# axiom_beta_sensor_cmv12000_tht_v0_16_r1_.net
KiCad netlist of a schematic drawn in EAGLE
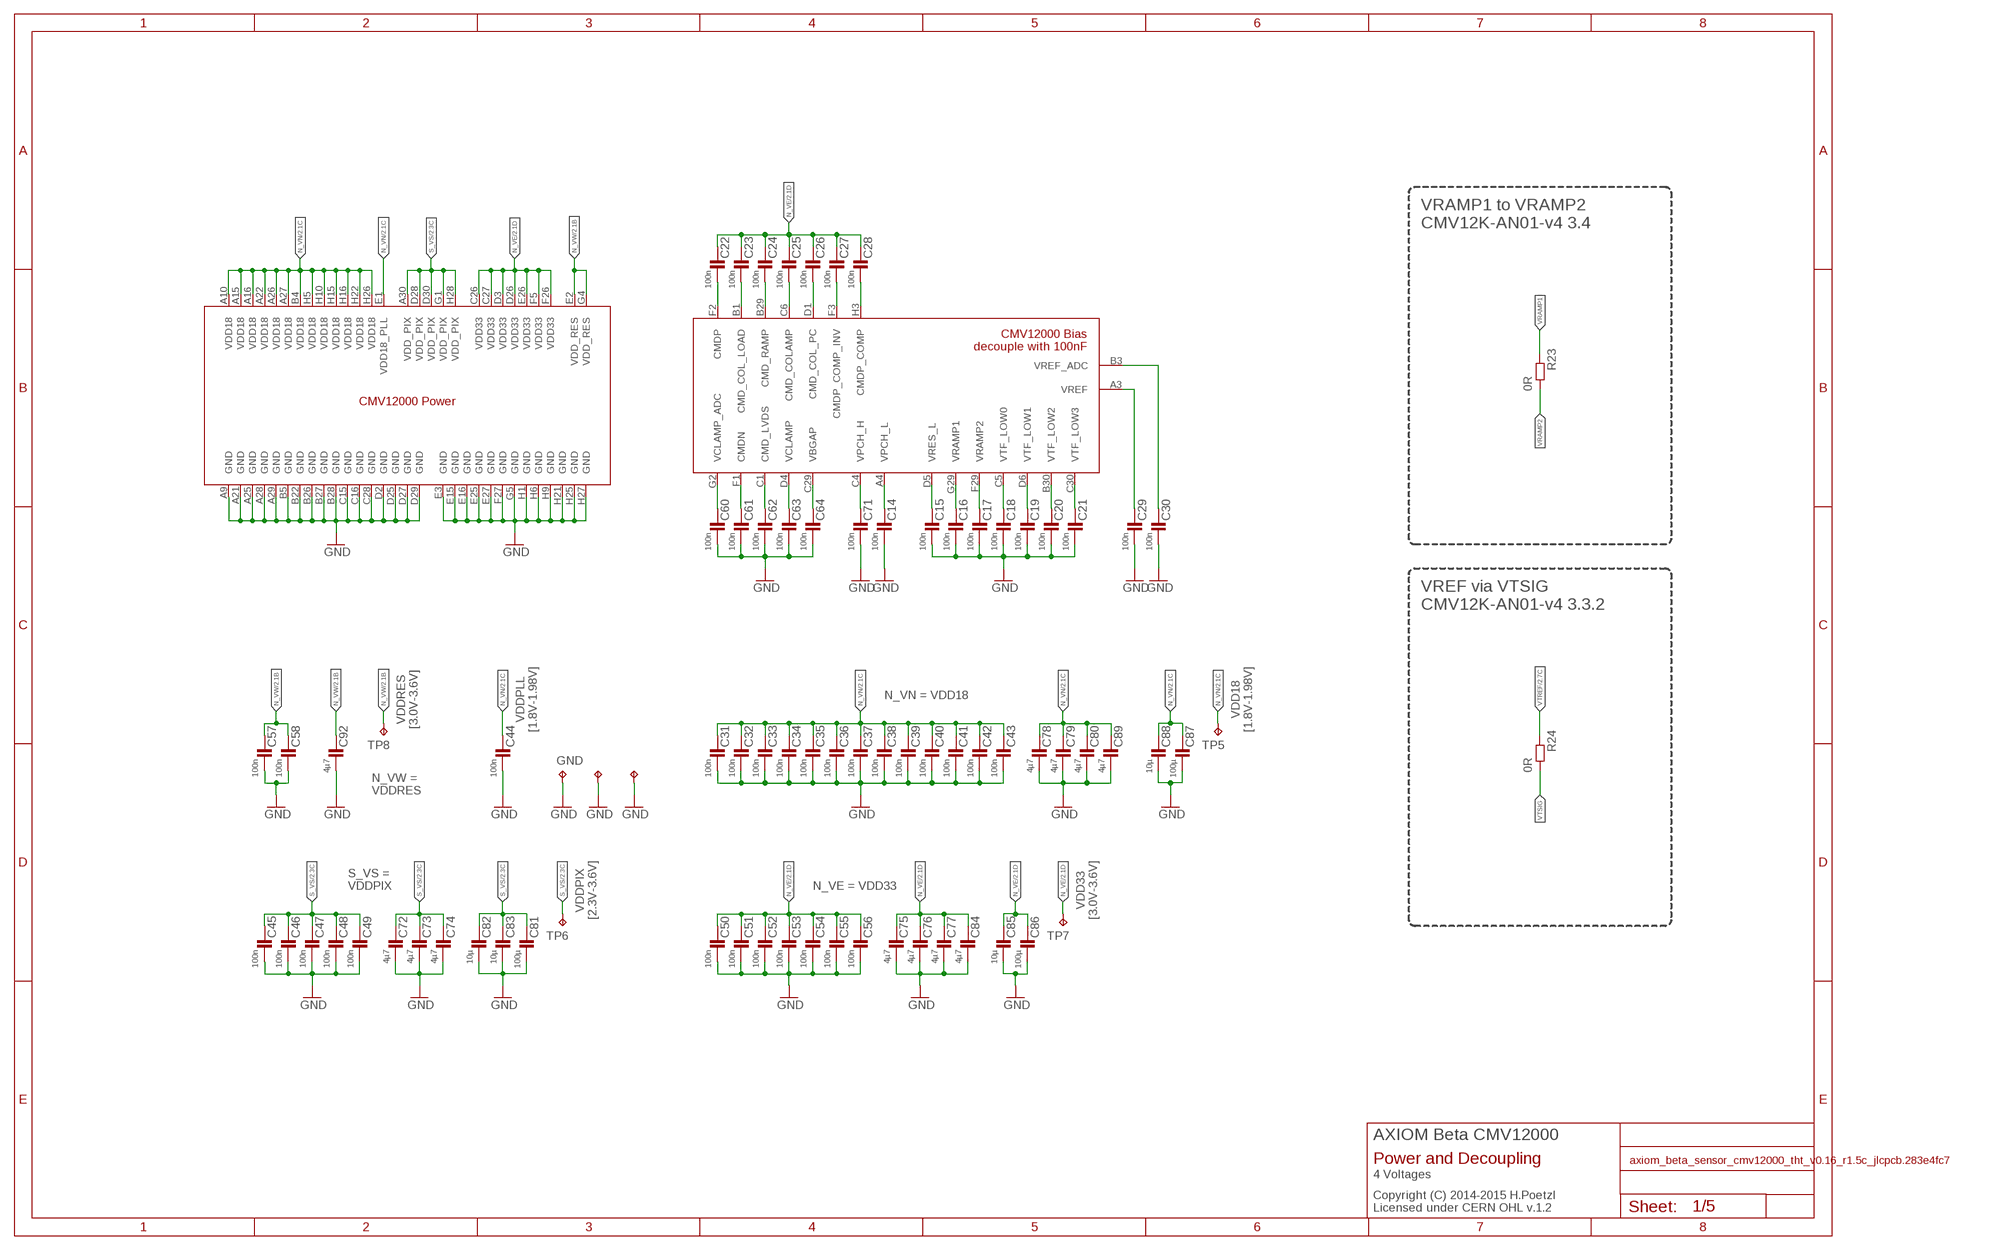
[diagram p0: schematic, sheet 1]
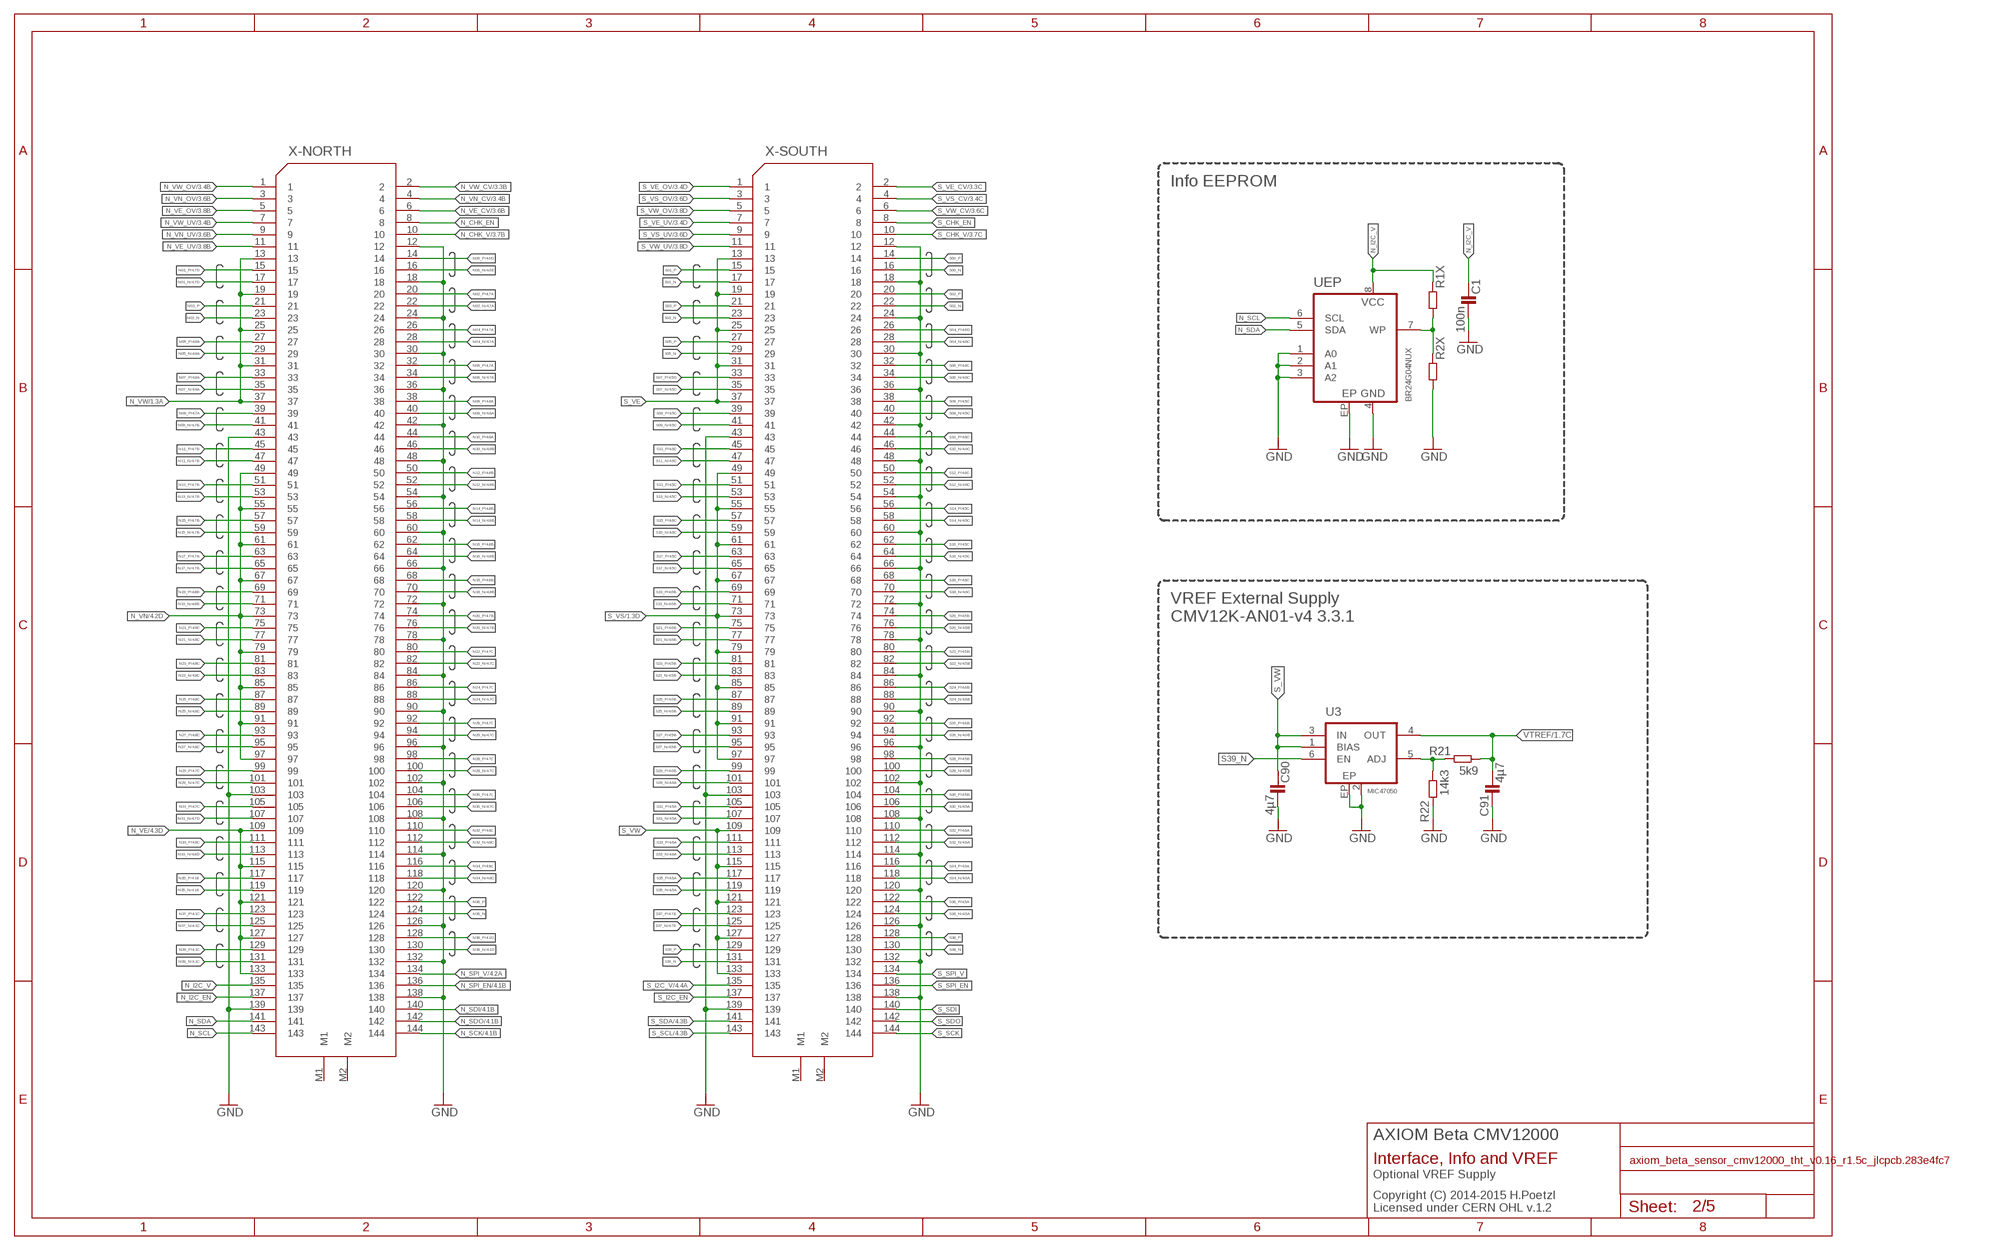
[diagram p1: schematic, sheet 2]
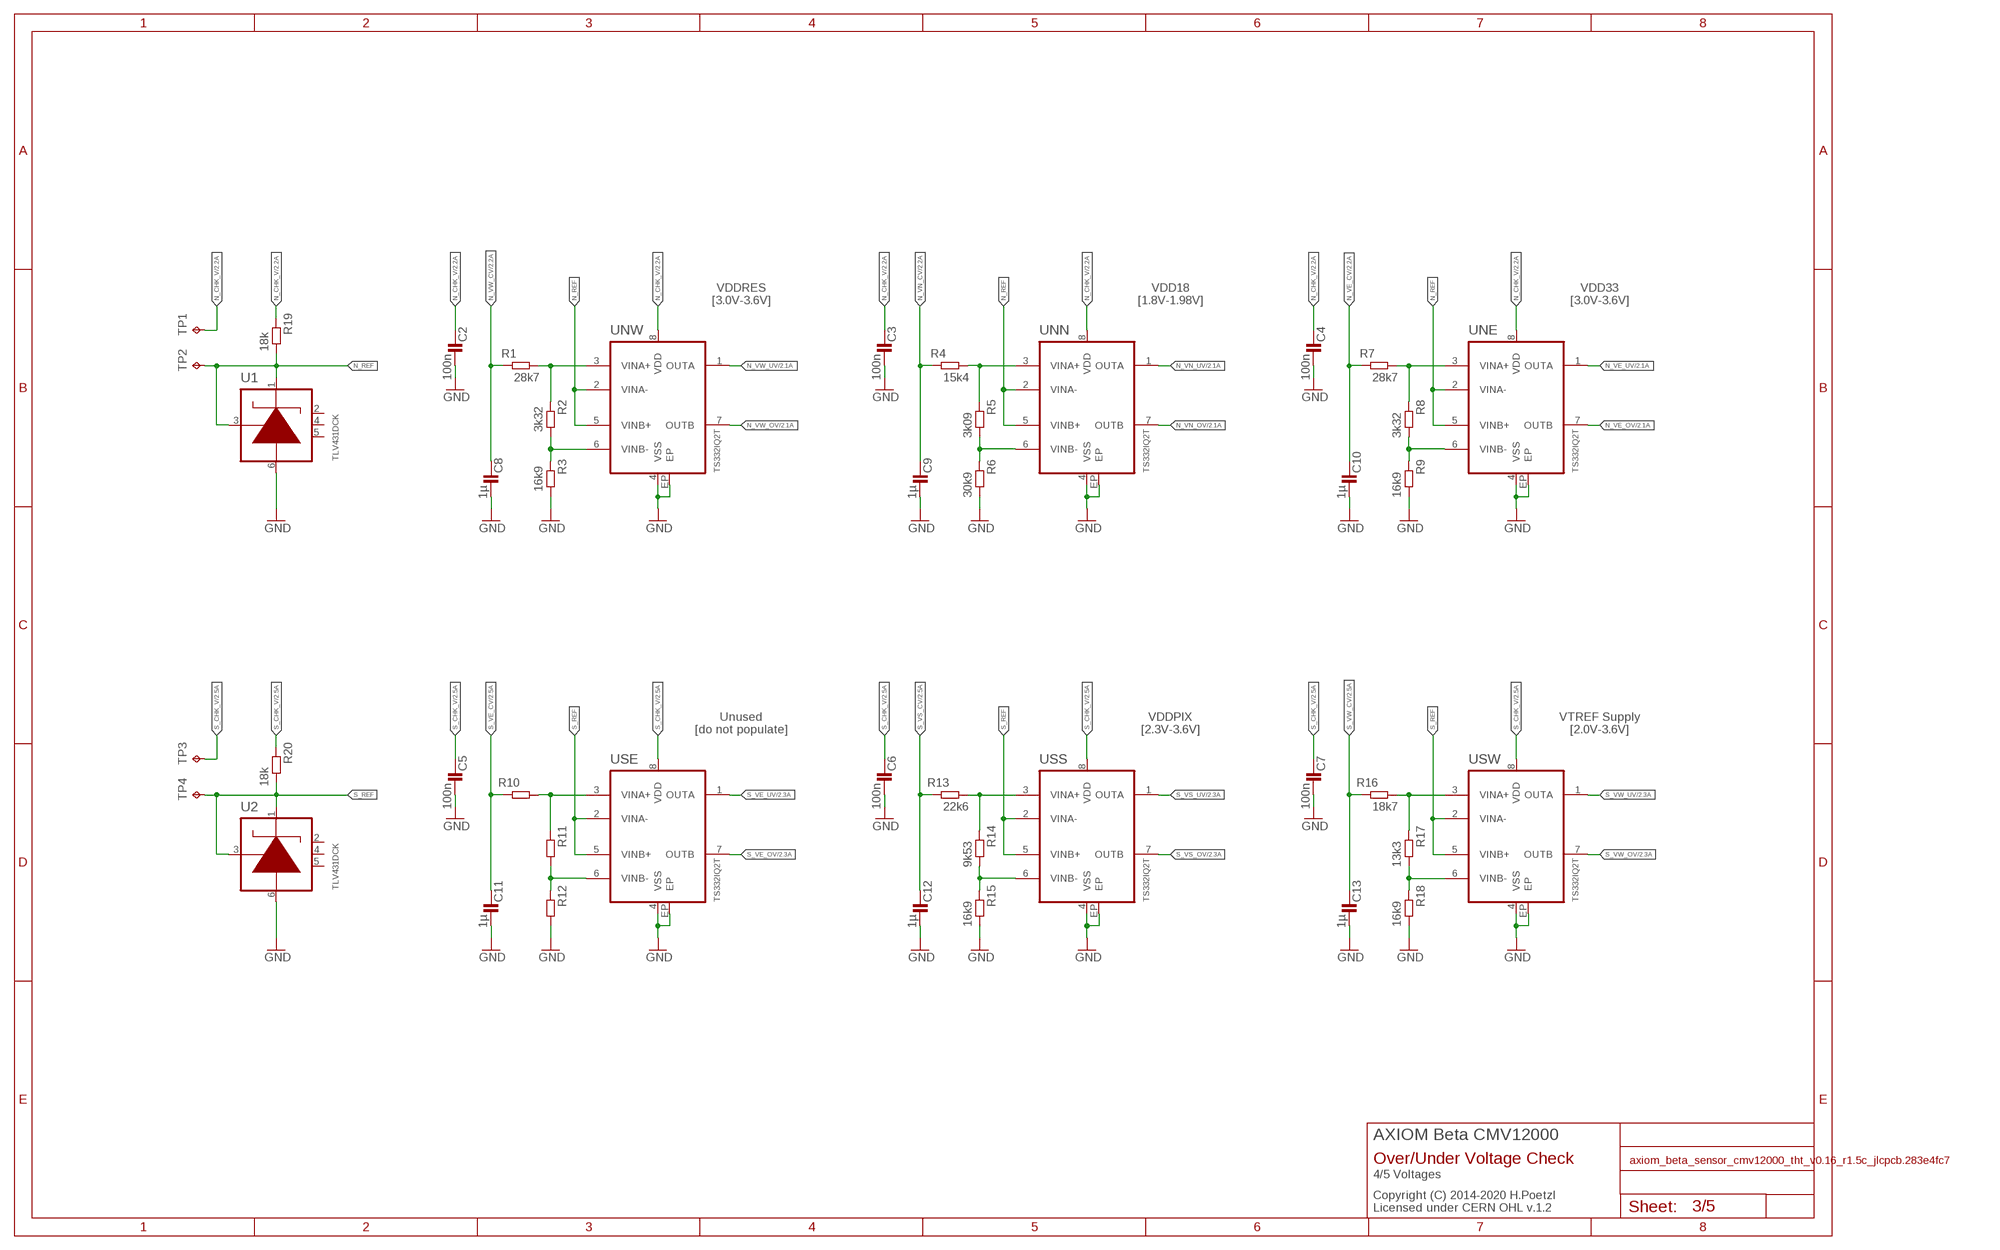
[diagram p2: schematic, sheet 3]
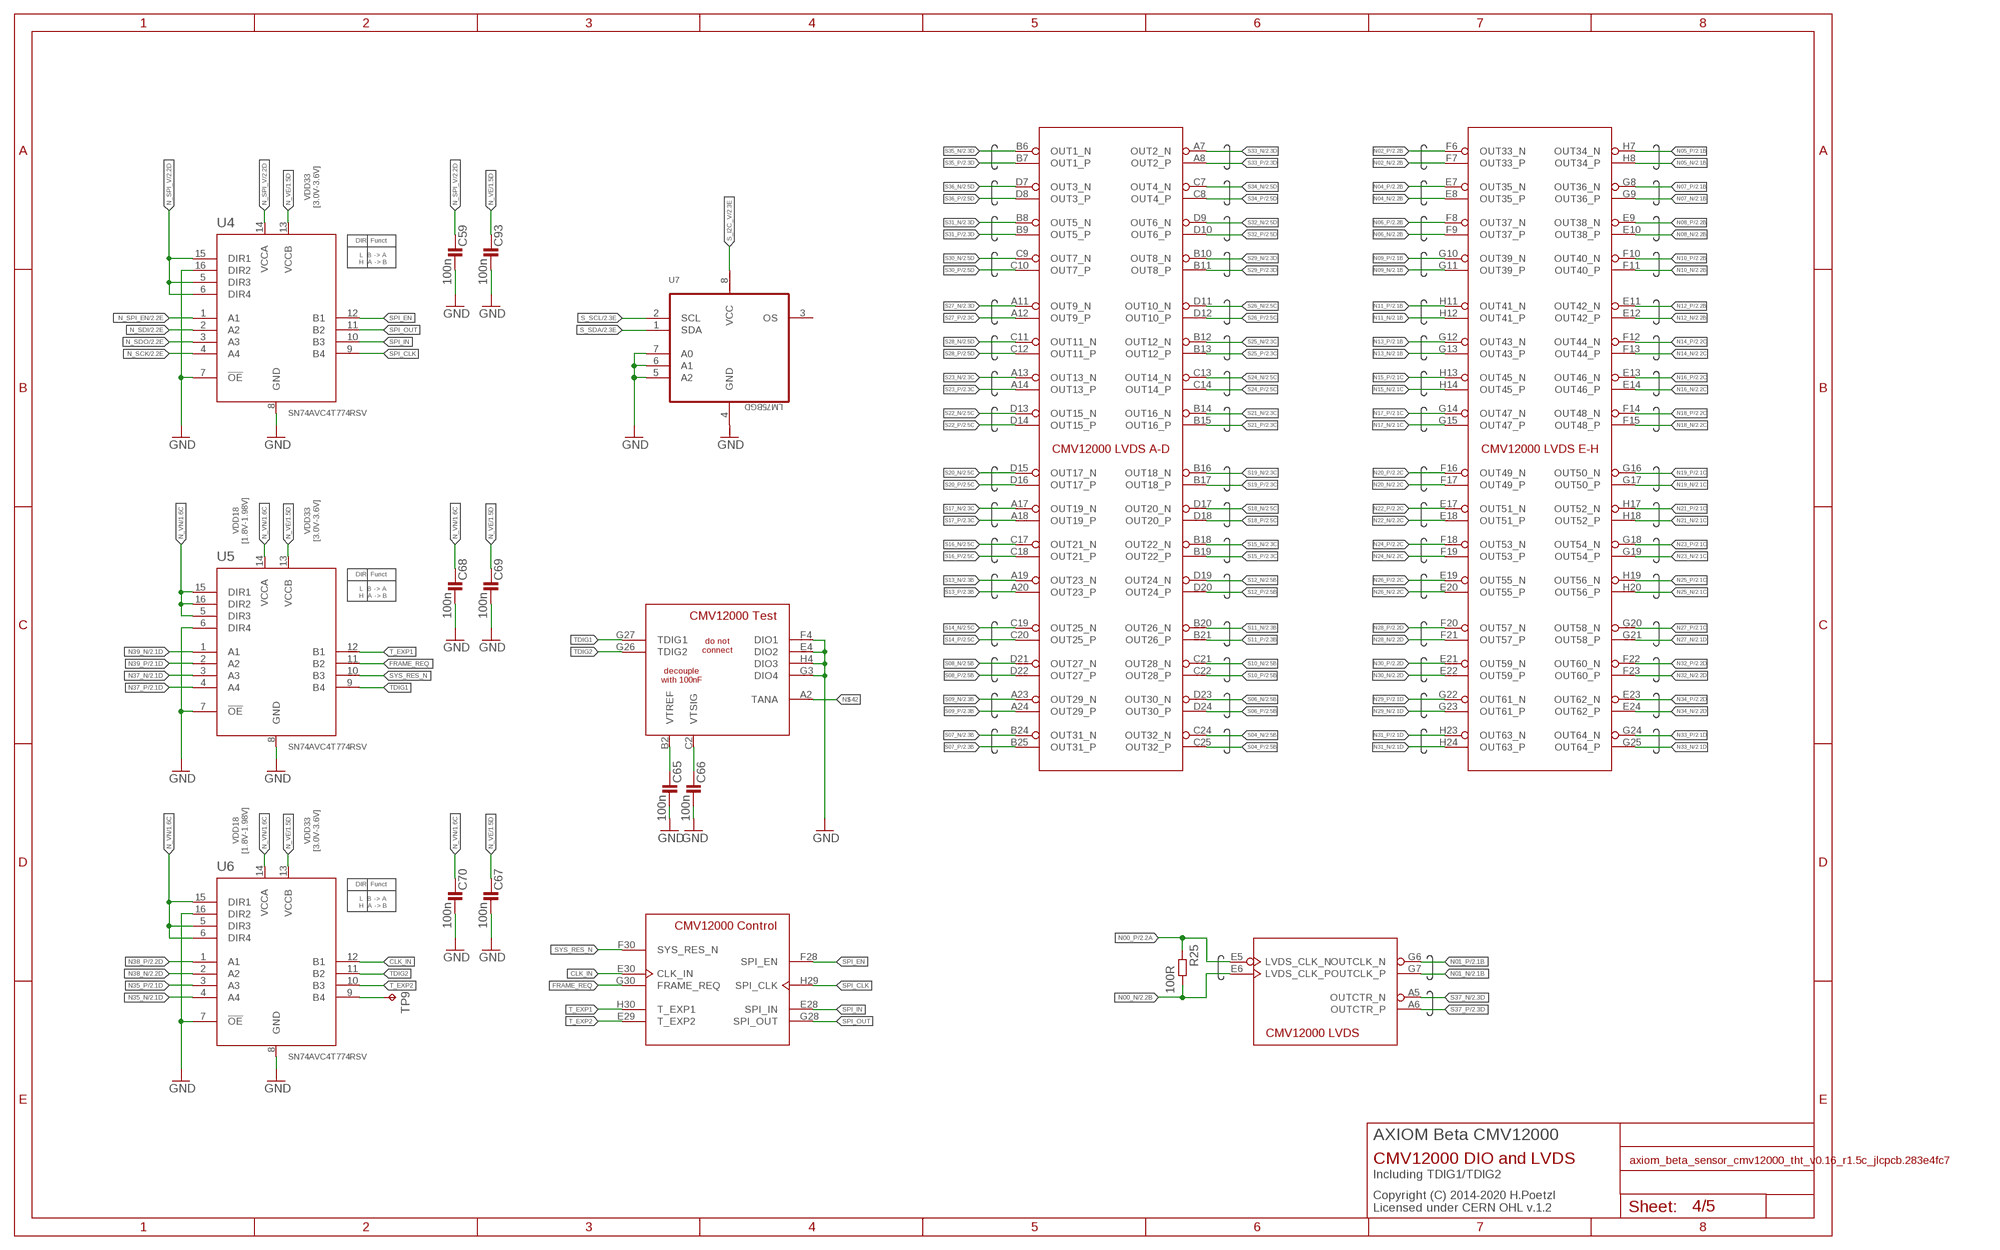
[diagram p3: schematic, sheet 4]
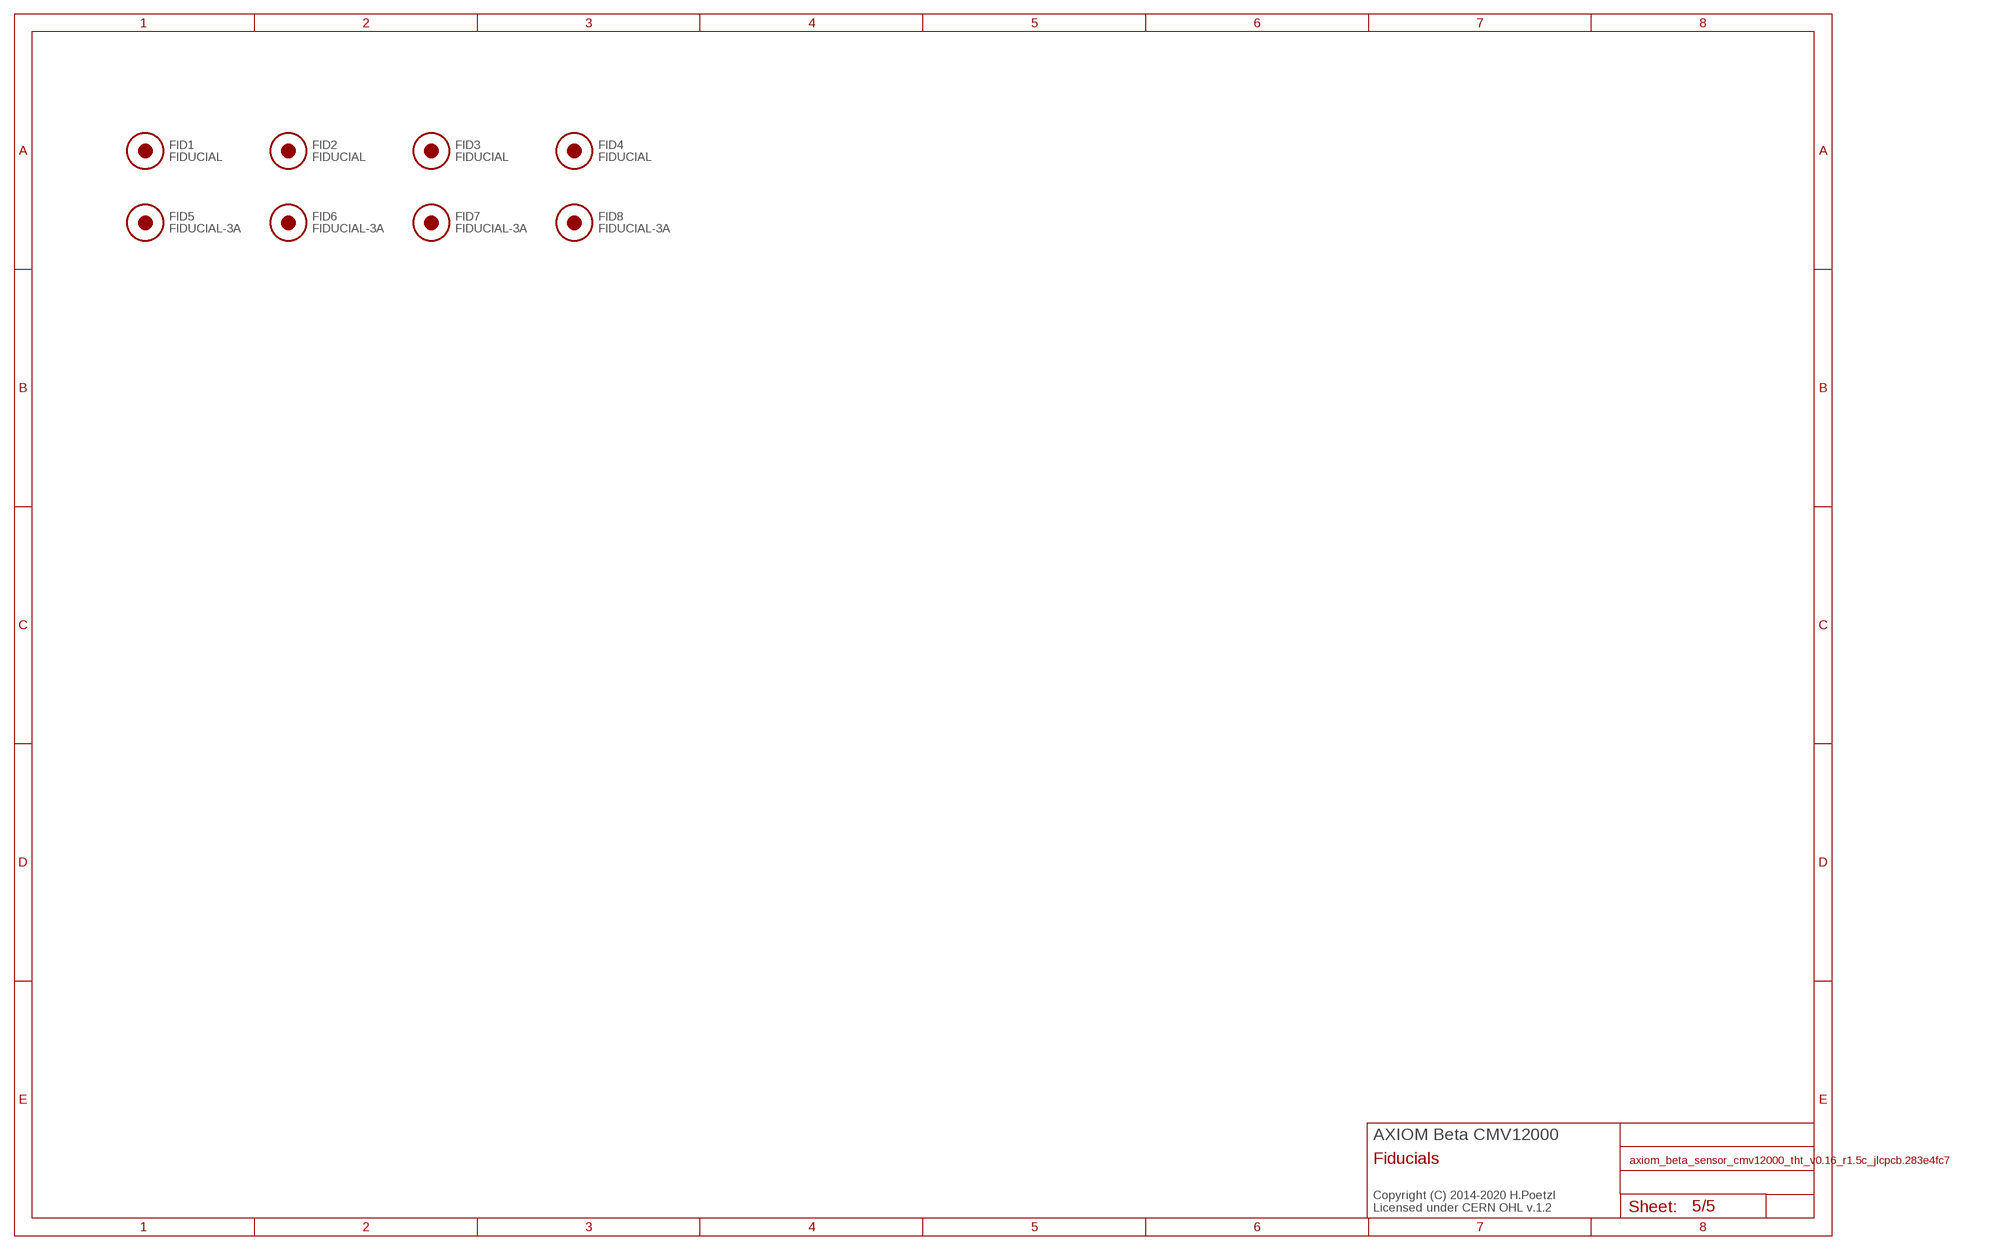
[diagram p4: schematic, sheet 5]

(export (version "E")
  (design (tool "Eeschema 10.0.6"))
  (components
    (comp (ref "FID1")
      (value "FIDUCIAL")
      (footprint "eagle-import:FID_ARROW")
      (libsource (lib "eagle-import") (part "FIDUCIAL"))
    )
    (comp (ref "FID2")
      (value "FIDUCIAL")
      (footprint "eagle-import:FID_ARROW")
      (libsource (lib "eagle-import") (part "FIDUCIAL"))
    )
    (comp (ref "FID3")
      (value "FIDUCIAL")
      (footprint "eagle-import:FID_ARROW")
      (libsource (lib "eagle-import") (part "FIDUCIAL"))
    )
    (comp (ref "FID4")
      (value "FIDUCIAL")
      (footprint "eagle-import:FID_ARROW")
      (libsource (lib "eagle-import") (part "FIDUCIAL"))
    )
    (comp (ref "FID5")
      (value "FIDUCIAL-3A")
      (footprint "eagle-import:FID_3ARROW")
      (libsource (lib "eagle-import") (part "FIDUCIAL-3A"))
    )
    (comp (ref "FID6")
      (value "FIDUCIAL-3A")
      (footprint "eagle-import:FID_3ARROW")
      (libsource (lib "eagle-import") (part "FIDUCIAL-3A"))
    )
    (comp (ref "FID7")
      (value "FIDUCIAL-3A")
      (footprint "eagle-import:FID_3ARROW")
      (libsource (lib "eagle-import") (part "FIDUCIAL-3A"))
    )
    (comp (ref "FID8")
      (value "FIDUCIAL-3A")
      (footprint "eagle-import:FID_3ARROW")
      (libsource (lib "eagle-import") (part "FIDUCIAL-3A"))
    )
    (comp (ref "C59")
      (value "100n")
      (footprint "eagle-import:0402-C")
      (libsource (lib "eagle-import") (part "C0402-C"))
    )
    (comp (ref "C65")
      (value "100n")
      (footprint "eagle-import:0402-C")
      (libsource (lib "eagle-import") (part "C0402-C"))
    )
    (comp (ref "C66")
      (value "100n")
      (footprint "eagle-import:0402-C")
      (libsource (lib "eagle-import") (part "C0402-C"))
    )
    (comp (ref "C67")
      (value "100n")
      (footprint "eagle-import:0402-C")
      (libsource (lib "eagle-import") (part "C0402-C"))
    )
    (comp (ref "C68")
      (value "100n")
      (footprint "eagle-import:0402-C")
      (libsource (lib "eagle-import") (part "C0402-C"))
    )
    (comp (ref "C69")
      (value "100n")
      (footprint "eagle-import:0402-C")
      (libsource (lib "eagle-import") (part "C0402-C"))
    )
    (comp (ref "C70")
      (value "100n")
      (footprint "eagle-import:0402-C")
      (libsource (lib "eagle-import") (part "C0402-C"))
    )
    (comp (ref "C93")
      (value "100n")
      (footprint "eagle-import:0402-C")
      (libsource (lib "eagle-import") (part "C0402-C"))
    )
    (comp (ref "R25")
      (value "100R")
      (footprint "eagle-import:0402-C")
      (libsource (lib "eagle-import") (part "R0402-C"))
    )
    (comp (ref "SENSOR")
      (value "CMV12000JLCPCB")
      (footprint "eagle-import:10-30-07-237-400T4-JLCPCB")
      (libsource (lib "eagle-import") (part "CMV12000JLCPCB"))
    )
    (comp (ref "TP9")
      (value "TPTP10R")
      (footprint "eagle-import:TP10R")
      (libsource (lib "eagle-import") (part "TPTP10R"))
    )
    (comp (ref "U4")
      (value "SN74AVC4T774RSV")
      (footprint "eagle-import:QFN40P185X265X55-16N")
      (libsource (lib "eagle-import") (part "SN74AVC4T774RSV"))
    )
    (comp (ref "U5")
      (value "SN74AVC4T774RSV")
      (footprint "eagle-import:QFN40P185X265X55-16N")
      (libsource (lib "eagle-import") (part "SN74AVC4T774RSV"))
    )
    (comp (ref "U6")
      (value "SN74AVC4T774RSV")
      (footprint "eagle-import:QFN40P185X265X55-16N")
      (libsource (lib "eagle-import") (part "SN74AVC4T774RSV"))
    )
    (comp (ref "U7")
      (value "LM75BGD")
      (footprint "eagle-import:SOT996-2_3")
      (libsource (lib "eagle-import") (part "LM75BGD"))
    )
    (comp (ref "C1")
      (value "100n")
      (footprint "eagle-import:0402-C")
      (libsource (lib "eagle-import") (part "C0402-C"))
    )
    (comp (ref "C90")
      (value "4µ7")
      (footprint "eagle-import:0402-C")
      (libsource (lib "eagle-import") (part "C0402-C"))
    )
    (comp (ref "C91")
      (value "4µ7")
      (footprint "eagle-import:0402-C")
      (libsource (lib "eagle-import") (part "C0402-C"))
    )
    (comp (ref "R1X")
      (value "R0402-C")
      (footprint "eagle-import:0402-C")
      (libsource (lib "eagle-import") (part "R0402-C"))
    )
    (comp (ref "R2X")
      (value "R0402-C")
      (footprint "eagle-import:0402-C")
      (libsource (lib "eagle-import") (part "R0402-C"))
    )
    (comp (ref "R21")
      (value "5k9")
      (footprint "eagle-import:0402-C")
      (libsource (lib "eagle-import") (part "R0402-C"))
    )
    (comp (ref "R22")
      (value "14k3")
      (footprint "eagle-import:0402-C")
      (libsource (lib "eagle-import") (part "R0402-C"))
    )
    (comp (ref "U3")
      (value "MIC47050")
      (footprint "eagle-import:MLF-6")
      (libsource (lib "eagle-import") (part "MIC47050-ADJ"))
    )
    (comp (ref "UEP")
      (value "BR24G04NUX")
      (footprint "eagle-import:DFN200X300X100-9N")
      (libsource (lib "eagle-import") (part "BR24G04NUX"))
    )
    (comp (ref "X-NORTH")
      (value "FX10-144P")
      (footprint "eagle-import:FX10A-144P")
      (libsource (lib "eagle-import") (part "FX10-144P"))
    )
    (comp (ref "X-SOUTH")
      (value "FX10-144P")
      (footprint "eagle-import:FX10A-144P")
      (libsource (lib "eagle-import") (part "FX10-144P"))
    )
    (comp (ref "C2")
      (value "100n")
      (footprint "eagle-import:0402-C")
      (libsource (lib "eagle-import") (part "C0402-C"))
    )
    (comp (ref "C3")
      (value "100n")
      (footprint "eagle-import:0402-C")
      (libsource (lib "eagle-import") (part "C0402-C"))
    )
    (comp (ref "C4")
      (value "100n")
      (footprint "eagle-import:0402-C")
      (libsource (lib "eagle-import") (part "C0402-C"))
    )
    (comp (ref "C5")
      (value "100n")
      (footprint "eagle-import:0402-C")
      (libsource (lib "eagle-import") (part "C0402-C"))
    )
    (comp (ref "C6")
      (value "100n")
      (footprint "eagle-import:0402-C")
      (libsource (lib "eagle-import") (part "C0402-C"))
    )
    (comp (ref "C7")
      (value "100n")
      (footprint "eagle-import:0402-C")
      (libsource (lib "eagle-import") (part "C0402-C"))
    )
    (comp (ref "C8")
      (value "1µ")
      (footprint "eagle-import:0402-C")
      (libsource (lib "eagle-import") (part "C0402-C"))
    )
    (comp (ref "C9")
      (value "1µ")
      (footprint "eagle-import:0402-C")
      (libsource (lib "eagle-import") (part "C0402-C"))
    )
    (comp (ref "C10")
      (value "1µ")
      (footprint "eagle-import:0402-C")
      (libsource (lib "eagle-import") (part "C0402-C"))
    )
    (comp (ref "C11")
      (value "1µ")
      (footprint "eagle-import:0402-C")
      (libsource (lib "eagle-import") (part "C0402-C"))
    )
    (comp (ref "C12")
      (value "1µ")
      (footprint "eagle-import:0402-C")
      (libsource (lib "eagle-import") (part "C0402-C"))
    )
    (comp (ref "C13")
      (value "1µ")
      (footprint "eagle-import:0402-C")
      (libsource (lib "eagle-import") (part "C0402-C"))
    )
    (comp (ref "R1")
      (value "28k7")
      (footprint "eagle-import:0402-C")
      (libsource (lib "eagle-import") (part "R0402-C"))
    )
    (comp (ref "R2")
      (value "3k32")
      (footprint "eagle-import:0402-C")
      (libsource (lib "eagle-import") (part "R0402-C"))
    )
    (comp (ref "R3")
      (value "16k9")
      (footprint "eagle-import:0402-C")
      (libsource (lib "eagle-import") (part "R0402-C"))
    )
    (comp (ref "R4")
      (value "15k4")
      (footprint "eagle-import:0402-C")
      (libsource (lib "eagle-import") (part "R0402-C"))
    )
    (comp (ref "R5")
      (value "3k09")
      (footprint "eagle-import:0402-C")
      (libsource (lib "eagle-import") (part "R0402-C"))
    )
    (comp (ref "R6")
      (value "30k9")
      (footprint "eagle-import:0402-C")
      (libsource (lib "eagle-import") (part "R0402-C"))
    )
    (comp (ref "R7")
      (value "28k7")
      (footprint "eagle-import:0402-C")
      (libsource (lib "eagle-import") (part "R0402-C"))
    )
    (comp (ref "R8")
      (value "3k32")
      (footprint "eagle-import:0402-C")
      (libsource (lib "eagle-import") (part "R0402-C"))
    )
    (comp (ref "R9")
      (value "16k9")
      (footprint "eagle-import:0402-C")
      (libsource (lib "eagle-import") (part "R0402-C"))
    )
    (comp (ref "R10")
      (value "R0402-C")
      (footprint "eagle-import:0402-C")
      (libsource (lib "eagle-import") (part "R0402-C"))
    )
    (comp (ref "R11")
      (value "R0402-C")
      (footprint "eagle-import:0402-C")
      (libsource (lib "eagle-import") (part "R0402-C"))
    )
    (comp (ref "R12")
      (value "R0402-C")
      (footprint "eagle-import:0402-C")
      (libsource (lib "eagle-import") (part "R0402-C"))
    )
    (comp (ref "R13")
      (value "22k6")
      (footprint "eagle-import:0402-C")
      (libsource (lib "eagle-import") (part "R0402-C"))
    )
    (comp (ref "R14")
      (value "9k53")
      (footprint "eagle-import:0402-C")
      (libsource (lib "eagle-import") (part "R0402-C"))
    )
    (comp (ref "R15")
      (value "16k9")
      (footprint "eagle-import:0402-C")
      (libsource (lib "eagle-import") (part "R0402-C"))
    )
    (comp (ref "R16")
      (value "18k7")
      (footprint "eagle-import:0402-C")
      (libsource (lib "eagle-import") (part "R0402-C"))
    )
    (comp (ref "R17")
      (value "13k3")
      (footprint "eagle-import:0402-C")
      (libsource (lib "eagle-import") (part "R0402-C"))
    )
    (comp (ref "R18")
      (value "16k9")
      (footprint "eagle-import:0402-C")
      (libsource (lib "eagle-import") (part "R0402-C"))
    )
    (comp (ref "R19")
      (value "18k")
      (footprint "eagle-import:0402-C")
      (libsource (lib "eagle-import") (part "R0402-C"))
    )
    (comp (ref "R20")
      (value "18k")
      (footprint "eagle-import:0402-C")
      (libsource (lib "eagle-import") (part "R0402-C"))
    )
    (comp (ref "TP1")
      (value "TPTP10R")
      (footprint "eagle-import:TP10R")
      (libsource (lib "eagle-import") (part "TPTP10R"))
    )
    (comp (ref "TP2")
      (value "TPTP10R")
      (footprint "eagle-import:TP10R")
      (libsource (lib "eagle-import") (part "TPTP10R"))
    )
    (comp (ref "TP3")
      (value "TPTP10R")
      (footprint "eagle-import:TP10R")
      (libsource (lib "eagle-import") (part "TPTP10R"))
    )
    (comp (ref "TP4")
      (value "TPTP10R")
      (footprint "eagle-import:TP10R")
      (libsource (lib "eagle-import") (part "TPTP10R"))
    )
    (comp (ref "U1")
      (value "TLV431DCK")
      (footprint "eagle-import:SOT65P210X110-6N")
      (libsource (lib "eagle-import") (part "TLV431DCK"))
    )
    (comp (ref "U2")
      (value "TLV431DCK")
      (footprint "eagle-import:SOT65P210X110-6N")
      (libsource (lib "eagle-import") (part "TLV431DCK"))
    )
    (comp (ref "UNE")
      (value "TS332IQ2T")
      (footprint "eagle-import:DFN200X200X100-9N")
      (libsource (lib "eagle-import") (part "TS332IQ2T"))
    )
    (comp (ref "UNN")
      (value "TS332IQ2T")
      (footprint "eagle-import:DFN200X200X100-9N")
      (libsource (lib "eagle-import") (part "TS332IQ2T"))
    )
    (comp (ref "UNW")
      (value "TS332IQ2T")
      (footprint "eagle-import:DFN200X200X100-9N")
      (libsource (lib "eagle-import") (part "TS332IQ2T"))
    )
    (comp (ref "USE")
      (value "TS332IQ2T")
      (footprint "eagle-import:DFN200X200X100-9N")
      (libsource (lib "eagle-import") (part "TS332IQ2T"))
    )
    (comp (ref "USS")
      (value "TS332IQ2T")
      (footprint "eagle-import:DFN200X200X100-9N")
      (libsource (lib "eagle-import") (part "TS332IQ2T"))
    )
    (comp (ref "USW")
      (value "TS332IQ2T")
      (footprint "eagle-import:DFN200X200X100-9N")
      (libsource (lib "eagle-import") (part "TS332IQ2T"))
    )
    (comp (ref "C14")
      (value "100n")
      (footprint "eagle-import:0402-C")
      (libsource (lib "eagle-import") (part "C0402-C"))
    )
    (comp (ref "C15")
      (value "100n")
      (footprint "eagle-import:0402-C")
      (libsource (lib "eagle-import") (part "C0402-C"))
    )
    (comp (ref "C16")
      (value "100n")
      (footprint "eagle-import:0402-C")
      (libsource (lib "eagle-import") (part "C0402-C"))
    )
    (comp (ref "C17")
      (value "100n")
      (footprint "eagle-import:0402-C")
      (libsource (lib "eagle-import") (part "C0402-C"))
    )
    (comp (ref "C18")
      (value "100n")
      (footprint "eagle-import:0402-C")
      (libsource (lib "eagle-import") (part "C0402-C"))
    )
    (comp (ref "C19")
      (value "100n")
      (footprint "eagle-import:0402-C")
      (libsource (lib "eagle-import") (part "C0402-C"))
    )
    (comp (ref "C20")
      (value "100n")
      (footprint "eagle-import:0402-C")
      (libsource (lib "eagle-import") (part "C0402-C"))
    )
    (comp (ref "C21")
      (value "100n")
      (footprint "eagle-import:0402-C")
      (libsource (lib "eagle-import") (part "C0402-C"))
    )
    (comp (ref "C22")
      (value "100n")
      (footprint "eagle-import:0402-C")
      (libsource (lib "eagle-import") (part "C0402-C"))
    )
    (comp (ref "C23")
      (value "100n")
      (footprint "eagle-import:0402-C")
      (libsource (lib "eagle-import") (part "C0402-C"))
    )
    (comp (ref "C24")
      (value "100n")
      (footprint "eagle-import:0402-C")
      (libsource (lib "eagle-import") (part "C0402-C"))
    )
    (comp (ref "C25")
      (value "100n")
      (footprint "eagle-import:0402-C")
      (libsource (lib "eagle-import") (part "C0402-C"))
    )
    (comp (ref "C26")
      (value "100n")
      (footprint "eagle-import:0402-C")
      (libsource (lib "eagle-import") (part "C0402-C"))
    )
    (comp (ref "C27")
      (value "100n")
      (footprint "eagle-import:0402-C")
      (libsource (lib "eagle-import") (part "C0402-C"))
    )
    (comp (ref "C28")
      (value "100n")
      (footprint "eagle-import:0402-C")
      (libsource (lib "eagle-import") (part "C0402-C"))
    )
    (comp (ref "C29")
      (value "100n")
      (footprint "eagle-import:0402-C")
      (libsource (lib "eagle-import") (part "C0402-C"))
    )
    (comp (ref "C30")
      (value "100n")
      (footprint "eagle-import:0402-C")
      (libsource (lib "eagle-import") (part "C0402-C"))
    )
    (comp (ref "C31")
      (value "100n")
      (footprint "eagle-import:0402-C")
      (libsource (lib "eagle-import") (part "C0402-C"))
    )
    (comp (ref "C32")
      (value "100n")
      (footprint "eagle-import:0402-C")
      (libsource (lib "eagle-import") (part "C0402-C"))
    )
    (comp (ref "C33")
      (value "100n")
      (footprint "eagle-import:0402-C")
      (libsource (lib "eagle-import") (part "C0402-C"))
    )
    (comp (ref "C34")
      (value "100n")
      (footprint "eagle-import:0402-C")
      (libsource (lib "eagle-import") (part "C0402-C"))
    )
    (comp (ref "C35")
      (value "100n")
      (footprint "eagle-import:0402-C")
      (libsource (lib "eagle-import") (part "C0402-C"))
    )
    (comp (ref "C36")
      (value "100n")
      (footprint "eagle-import:0402-C")
      (libsource (lib "eagle-import") (part "C0402-C"))
    )
    (comp (ref "C37")
      (value "100n")
      (footprint "eagle-import:0402-C")
      (libsource (lib "eagle-import") (part "C0402-C"))
    )
    (comp (ref "C38")
      (value "100n")
      (footprint "eagle-import:0402-C")
      (libsource (lib "eagle-import") (part "C0402-C"))
    )
    (comp (ref "C39")
      (value "100n")
      (footprint "eagle-import:0402-C")
      (libsource (lib "eagle-import") (part "C0402-C"))
    )
    (comp (ref "C40")
      (value "100n")
      (footprint "eagle-import:0402-C")
      (libsource (lib "eagle-import") (part "C0402-C"))
    )
    (comp (ref "C41")
      (value "100n")
      (footprint "eagle-import:0402-C")
      (libsource (lib "eagle-import") (part "C0402-C"))
    )
    (comp (ref "C42")
      (value "100n")
      (footprint "eagle-import:0402-C")
      (libsource (lib "eagle-import") (part "C0402-C"))
    )
    (comp (ref "C43")
      (value "100n")
      (footprint "eagle-import:0402-C")
      (libsource (lib "eagle-import") (part "C0402-C"))
    )
    (comp (ref "C44")
      (value "100n")
      (footprint "eagle-import:0402-C")
      (libsource (lib "eagle-import") (part "C0402-C"))
    )
    (comp (ref "C45")
      (value "100n")
      (footprint "eagle-import:0402-C")
      (libsource (lib "eagle-import") (part "C0402-C"))
    )
    (comp (ref "C46")
      (value "100n")
      (footprint "eagle-import:0402-C")
      (libsource (lib "eagle-import") (part "C0402-C"))
    )
    (comp (ref "C47")
      (value "100n")
      (footprint "eagle-import:0402-C")
      (libsource (lib "eagle-import") (part "C0402-C"))
    )
    (comp (ref "C48")
      (value "100n")
      (footprint "eagle-import:0402-C")
      (libsource (lib "eagle-import") (part "C0402-C"))
    )
    (comp (ref "C49")
      (value "100n")
      (footprint "eagle-import:0402-C")
      (libsource (lib "eagle-import") (part "C0402-C"))
    )
    (comp (ref "C50")
      (value "100n")
      (footprint "eagle-import:0402-C")
      (libsource (lib "eagle-import") (part "C0402-C"))
    )
    (comp (ref "C51")
      (value "100n")
      (footprint "eagle-import:0402-C")
      (libsource (lib "eagle-import") (part "C0402-C"))
    )
    (comp (ref "C52")
      (value "100n")
      (footprint "eagle-import:0402-C")
      (libsource (lib "eagle-import") (part "C0402-C"))
    )
    (comp (ref "C53")
      (value "100n")
      (footprint "eagle-import:0402-C")
      (libsource (lib "eagle-import") (part "C0402-C"))
    )
    (comp (ref "C54")
      (value "100n")
      (footprint "eagle-import:0402-C")
      (libsource (lib "eagle-import") (part "C0402-C"))
    )
    (comp (ref "C55")
      (value "100n")
      (footprint "eagle-import:0402-C")
      (libsource (lib "eagle-import") (part "C0402-C"))
    )
    (comp (ref "C56")
      (value "100n")
      (footprint "eagle-import:0402-C")
      (libsource (lib "eagle-import") (part "C0402-C"))
    )
    (comp (ref "C57")
      (value "100n")
      (footprint "eagle-import:0402-C")
      (libsource (lib "eagle-import") (part "C0402-C"))
    )
    (comp (ref "C58")
      (value "100n")
      (footprint "eagle-import:0402-C")
      (libsource (lib "eagle-import") (part "C0402-C"))
    )
    (comp (ref "C60")
      (value "100n")
      (footprint "eagle-import:0402-C")
      (libsource (lib "eagle-import") (part "C0402-C"))
    )
    (comp (ref "C61")
      (value "100n")
      (footprint "eagle-import:0402-C")
      (libsource (lib "eagle-import") (part "C0402-C"))
    )
    (comp (ref "C62")
      (value "100n")
      (footprint "eagle-import:0402-C")
      (libsource (lib "eagle-import") (part "C0402-C"))
    )
    (comp (ref "C63")
      (value "100n")
      (footprint "eagle-import:0402-C")
      (libsource (lib "eagle-import") (part "C0402-C"))
    )
    (comp (ref "C64")
      (value "100n")
      (footprint "eagle-import:0402-C")
      (libsource (lib "eagle-import") (part "C0402-C"))
    )
    (comp (ref "C71")
      (value "100n")
      (footprint "eagle-import:0402-C")
      (libsource (lib "eagle-import") (part "C0402-C"))
    )
    (comp (ref "C72")
      (value "4µ7")
      (footprint "eagle-import:0402-B")
      (libsource (lib "eagle-import") (part "C0402-B"))
    )
    (comp (ref "C73")
      (value "4µ7")
      (footprint "eagle-import:0402-C")
      (libsource (lib "eagle-import") (part "C0402-C"))
    )
    (comp (ref "C74")
      (value "4µ7")
      (footprint "eagle-import:0402-C")
      (libsource (lib "eagle-import") (part "C0402-C"))
    )
    (comp (ref "C75")
      (value "4µ7")
      (footprint "eagle-import:0402-C")
      (libsource (lib "eagle-import") (part "C0402-C"))
    )
    (comp (ref "C76")
      (value "4µ7")
      (footprint "eagle-import:0402-C")
      (libsource (lib "eagle-import") (part "C0402-C"))
    )
    (comp (ref "C77")
      (value "4µ7")
      (footprint "eagle-import:0402-B")
      (libsource (lib "eagle-import") (part "C0402-B"))
    )
    (comp (ref "C78")
      (value "4µ7")
      (footprint "eagle-import:0402-B")
      (libsource (lib "eagle-import") (part "C0402-B"))
    )
    (comp (ref "C79")
      (value "4µ7")
      (footprint "eagle-import:0402-C")
      (libsource (lib "eagle-import") (part "C0402-C"))
    )
    (comp (ref "C80")
      (value "4µ7")
      (footprint "eagle-import:0402-C")
      (libsource (lib "eagle-import") (part "C0402-C"))
    )
    (comp (ref "C81")
      (value "100µ")
      (footprint "eagle-import:1206-B")
      (libsource (lib "eagle-import") (part "C1206-B"))
    )
    (comp (ref "C82")
      (value "10µ")
      (footprint "eagle-import:0603-C")
      (libsource (lib "eagle-import") (part "C0603-C"))
    )
    (comp (ref "C83")
      (value "10µ")
      (footprint "eagle-import:0603-C")
      (libsource (lib "eagle-import") (part "C0603-C"))
    )
    (comp (ref "C84")
      (value "4µ7")
      (footprint "eagle-import:0402-C")
      (libsource (lib "eagle-import") (part "C0402-C"))
    )
    (comp (ref "C85")
      (value "10µ")
      (footprint "eagle-import:0603-C")
      (libsource (lib "eagle-import") (part "C0603-C"))
    )
    (comp (ref "C86")
      (value "100µ")
      (footprint "eagle-import:1206-B")
      (libsource (lib "eagle-import") (part "C1206-B"))
    )
    (comp (ref "C87")
      (value "100µ")
      (footprint "eagle-import:1206-B")
      (libsource (lib "eagle-import") (part "C1206-B"))
    )
    (comp (ref "C88")
      (value "10µ")
      (footprint "eagle-import:0603-C")
      (libsource (lib "eagle-import") (part "C0603-C"))
    )
    (comp (ref "C89")
      (value "4µ7")
      (footprint "eagle-import:0402-C")
      (libsource (lib "eagle-import") (part "C0402-C"))
    )
    (comp (ref "C92")
      (value "4µ7")
      (footprint "eagle-import:0402-C")
      (libsource (lib "eagle-import") (part "C0402-C"))
    )
    (comp (ref "GND")
      (value "TPTP10R")
      (footprint "eagle-import:TP10R")
      (libsource (lib "eagle-import") (part "TPTP10R"))
    )
    (comp (ref "GND75")
      (value "TPTP10R")
      (footprint "eagle-import:TP10R")
      (libsource (lib "eagle-import") (part "TPTP10R"))
    )
    (comp (ref "GND77")
      (value "TPTP10R")
      (footprint "eagle-import:TP10R")
      (libsource (lib "eagle-import") (part "TPTP10R"))
    )
    (comp (ref "R23")
      (value "0R")
      (footprint "eagle-import:0402-C")
      (libsource (lib "eagle-import") (part "R0402-C"))
    )
    (comp (ref "R24")
      (value "0R")
      (footprint "eagle-import:0402-C")
      (libsource (lib "eagle-import") (part "R0402-C"))
    )
    (comp (ref "TP5")
      (value "TPTP10R")
      (footprint "eagle-import:TP10R")
      (libsource (lib "eagle-import") (part "TPTP10R"))
    )
    (comp (ref "TP6")
      (value "TPTP10R")
      (footprint "eagle-import:TP10R")
      (libsource (lib "eagle-import") (part "TPTP10R"))
    )
    (comp (ref "TP7")
      (value "TPTP10R")
      (footprint "eagle-import:TP10R")
      (libsource (lib "eagle-import") (part "TPTP10R"))
    )
    (comp (ref "TP8")
      (value "TPTP10R")
      (footprint "eagle-import:TP10R")
      (libsource (lib "eagle-import") (part "TPTP10R"))
    )
  )
  (nets
    (net (code "1") (name "CLK_IN") (class "Default")
      (node (ref "SENSOR") (pin "E30") (pinfunction "CLK_IN_E30") (pintype "input"))
      (node (ref "U6") (pin "12") (pinfunction "B1_12") (pintype "bidirectional"))
    )
    (net (code "2") (name "FRAME_REQ") (class "Default")
      (node (ref "SENSOR") (pin "G30") (pinfunction "FRAME_REQ_G30") (pintype "input"))
      (node (ref "U5") (pin "11") (pinfunction "B2_11") (pintype "bidirectional"))
    )
    (net (code "3") (name "GND") (class "Default")
      (node (ref "C1") (pin "2") (pinfunction "2_2") (pintype "passive"))
      (node (ref "C10") (pin "2") (pinfunction "2_2") (pintype "passive"))
      (node (ref "C11") (pin "2") (pinfunction "2_2") (pintype "passive"))
      (node (ref "C12") (pin "2") (pinfunction "2_2") (pintype "passive"))
      (node (ref "C13") (pin "2") (pinfunction "2_2") (pintype "passive"))
      (node (ref "C14") (pin "2") (pinfunction "2_2") (pintype "passive"))
      (node (ref "C15") (pin "2") (pinfunction "2_2") (pintype "passive"))
      (node (ref "C16") (pin "2") (pinfunction "2_2") (pintype "passive"))
      (node (ref "C17") (pin "2") (pinfunction "2_2") (pintype "passive"))
      (node (ref "C18") (pin "2") (pinfunction "2_2") (pintype "passive"))
      (node (ref "C19") (pin "2") (pinfunction "2_2") (pintype "passive"))
      (node (ref "C2") (pin "2") (pinfunction "2_2") (pintype "passive"))
      (node (ref "C20") (pin "2") (pinfunction "2_2") (pintype "passive"))
      (node (ref "C21") (pin "2") (pinfunction "2_2") (pintype "passive"))
      (node (ref "C29") (pin "2") (pinfunction "2_2") (pintype "passive"))
      (node (ref "C3") (pin "2") (pinfunction "2_2") (pintype "passive"))
      (node (ref "C30") (pin "2") (pinfunction "2_2") (pintype "passive"))
      (node (ref "C31") (pin "2") (pinfunction "2_2") (pintype "passive"))
      (node (ref "C32") (pin "2") (pinfunction "2_2") (pintype "passive"))
      (node (ref "C33") (pin "2") (pinfunction "2_2") (pintype "passive"))
      (node (ref "C34") (pin "2") (pinfunction "2_2") (pintype "passive"))
      (node (ref "C35") (pin "2") (pinfunction "2_2") (pintype "passive"))
      (node (ref "C36") (pin "2") (pinfunction "2_2") (pintype "passive"))
      (node (ref "C37") (pin "2") (pinfunction "2_2") (pintype "passive"))
      (node (ref "C38") (pin "2") (pinfunction "2_2") (pintype "passive"))
      (node (ref "C39") (pin "2") (pinfunction "2_2") (pintype "passive"))
      (node (ref "C4") (pin "2") (pinfunction "2_2") (pintype "passive"))
      (node (ref "C40") (pin "2") (pinfunction "2_2") (pintype "passive"))
      (node (ref "C41") (pin "2") (pinfunction "2_2") (pintype "passive"))
      (node (ref "C42") (pin "2") (pinfunction "2_2") (pintype "passive"))
      (node (ref "C43") (pin "2") (pinfunction "2_2") (pintype "passive"))
      (node (ref "C44") (pin "2") (pinfunction "2_2") (pintype "passive"))
      (node (ref "C45") (pin "2") (pinfunction "2_2") (pintype "passive"))
      (node (ref "C46") (pin "2") (pinfunction "2_2") (pintype "passive"))
      (node (ref "C47") (pin "2") (pinfunction "2_2") (pintype "passive"))
      (node (ref "C48") (pin "2") (pinfunction "2_2") (pintype "passive"))
      (node (ref "C49") (pin "2") (pinfunction "2_2") (pintype "passive"))
      (node (ref "C5") (pin "2") (pinfunction "2_2") (pintype "passive"))
      (node (ref "C50") (pin "2") (pinfunction "2_2") (pintype "passive"))
      (node (ref "C51") (pin "2") (pinfunction "2_2") (pintype "passive"))
      (node (ref "C52") (pin "2") (pinfunction "2_2") (pintype "passive"))
      (node (ref "C53") (pin "2") (pinfunction "2_2") (pintype "passive"))
      (node (ref "C54") (pin "2") (pinfunction "2_2") (pintype "passive"))
      (node (ref "C55") (pin "2") (pinfunction "2_2") (pintype "passive"))
      (node (ref "C56") (pin "2") (pinfunction "2_2") (pintype "passive"))
      (node (ref "C57") (pin "2") (pinfunction "2_2") (pintype "passive"))
      (node (ref "C58") (pin "2") (pinfunction "2_2") (pintype "passive"))
      (node (ref "C59") (pin "2") (pinfunction "2_2") (pintype "passive"))
      (node (ref "C6") (pin "2") (pinfunction "2_2") (pintype "passive"))
      (node (ref "C60") (pin "2") (pinfunction "2_2") (pintype "passive"))
      (node (ref "C61") (pin "2") (pinfunction "2_2") (pintype "passive"))
      (node (ref "C62") (pin "2") (pinfunction "2_2") (pintype "passive"))
      (node (ref "C63") (pin "2") (pinfunction "2_2") (pintype "passive"))
      (node (ref "C64") (pin "2") (pinfunction "2_2") (pintype "passive"))
      (node (ref "C65") (pin "2") (pinfunction "2_2") (pintype "passive"))
      (node (ref "C66") (pin "2") (pinfunction "2_2") (pintype "passive"))
      (node (ref "C67") (pin "2") (pinfunction "2_2") (pintype "passive"))
      (node (ref "C68") (pin "2") (pinfunction "2_2") (pintype "passive"))
      (node (ref "C69") (pin "2") (pinfunction "2_2") (pintype "passive"))
      (node (ref "C7") (pin "2") (pinfunction "2_2") (pintype "passive"))
      (node (ref "C70") (pin "2") (pinfunction "2_2") (pintype "passive"))
      (node (ref "C71") (pin "2") (pinfunction "2_2") (pintype "passive"))
      (node (ref "C72") (pin "2") (pinfunction "2_2") (pintype "passive"))
      (node (ref "C73") (pin "2") (pinfunction "2_2") (pintype "passive"))
      (node (ref "C74") (pin "2") (pinfunction "2_2") (pintype "passive"))
      (node (ref "C75") (pin "2") (pinfunction "2_2") (pintype "passive"))
      (node (ref "C76") (pin "2") (pinfunction "2_2") (pintype "passive"))
      (node (ref "C77") (pin "2") (pinfunction "2_2") (pintype "passive"))
      (node (ref "C78") (pin "2") (pinfunction "2_2") (pintype "passive"))
      (node (ref "C79") (pin "2") (pinfunction "2_2") (pintype "passive"))
      (node (ref "C8") (pin "2") (pinfunction "2_2") (pintype "passive"))
      (node (ref "C80") (pin "2") (pinfunction "2_2") (pintype "passive"))
      (node (ref "C81") (pin "2") (pinfunction "2_2") (pintype "passive"))
      (node (ref "C82") (pin "2") (pinfunction "2_2") (pintype "passive"))
      (node (ref "C83") (pin "2") (pinfunction "2_2") (pintype "passive"))
      (node (ref "C84") (pin "2") (pinfunction "2_2") (pintype "passive"))
      (node (ref "C85") (pin "2") (pinfunction "2_2") (pintype "passive"))
      (node (ref "C86") (pin "2") (pinfunction "2_2") (pintype "passive"))
      (node (ref "C87") (pin "2") (pinfunction "2_2") (pintype "passive"))
      (node (ref "C88") (pin "2") (pinfunction "2_2") (pintype "passive"))
      (node (ref "C89") (pin "2") (pinfunction "2_2") (pintype "passive"))
      (node (ref "C9") (pin "2") (pinfunction "2_2") (pintype "passive"))
      (node (ref "C90") (pin "2") (pinfunction "2_2") (pintype "passive"))
      (node (ref "C91") (pin "1") (pinfunction "1_1") (pintype "passive"))
      (node (ref "C92") (pin "2") (pinfunction "2_2") (pintype "passive"))
      (node (ref "C93") (pin "2") (pinfunction "2_2") (pintype "passive"))
      (node (ref "GND") (pin "TP") (pinfunction "TP_TP") (pintype "input"))
      (node (ref "GND75") (pin "TP") (pinfunction "TP_TP") (pintype "input"))
      (node (ref "GND77") (pin "TP") (pinfunction "TP_TP") (pintype "input"))
      (node (ref "R12") (pin "2") (pinfunction "2_2") (pintype "passive"))
      (node (ref "R15") (pin "2") (pinfunction "2_2") (pintype "passive"))
      (node (ref "R18") (pin "2") (pinfunction "2_2") (pintype "passive"))
      (node (ref "R22") (pin "1") (pinfunction "1_1") (pintype "passive"))
      (node (ref "R2X") (pin "2") (pinfunction "2_2") (pintype "passive"))
      (node (ref "R3") (pin "2") (pinfunction "2_2") (pintype "passive"))
      (node (ref "R6") (pin "2") (pinfunction "2_2") (pintype "passive"))
      (node (ref "R9") (pin "2") (pinfunction "2_2") (pintype "passive"))
      (node (ref "SENSOR") (pin "A21") (pinfunction "GND_A21") (pintype "power_in"))
      (node (ref "SENSOR") (pin "A25") (pinfunction "GND_A25") (pintype "power_in"))
      (node (ref "SENSOR") (pin "A28") (pinfunction "GND_A28") (pintype "power_in"))
      (node (ref "SENSOR") (pin "A29") (pinfunction "GND_A29") (pintype "power_in"))
      (node (ref "SENSOR") (pin "A9") (pinfunction "GND_A9") (pintype "power_in"))
      (node (ref "SENSOR") (pin "B22") (pinfunction "GND_B22") (pintype "power_in"))
      (node (ref "SENSOR") (pin "B26") (pinfunction "GND_B26") (pintype "power_in"))
      (node (ref "SENSOR") (pin "B27") (pinfunction "GND_B27") (pintype "power_in"))
      (node (ref "SENSOR") (pin "B28") (pinfunction "GND_B28") (pintype "power_in"))
      (node (ref "SENSOR") (pin "B5") (pinfunction "GND_B5") (pintype "power_in"))
      (node (ref "SENSOR") (pin "C15") (pinfunction "GND_C15") (pintype "power_in"))
      (node (ref "SENSOR") (pin "C16") (pinfunction "GND_C16") (pintype "power_in"))
      (node (ref "SENSOR") (pin "C28") (pinfunction "GND_C28") (pintype "power_in"))
      (node (ref "SENSOR") (pin "D2") (pinfunction "GND_D2") (pintype "power_in"))
      (node (ref "SENSOR") (pin "D25") (pinfunction "GND_D25") (pintype "power_in"))
      (node (ref "SENSOR") (pin "D27") (pinfunction "GND_D27") (pintype "power_in"))
      (node (ref "SENSOR") (pin "D29") (pinfunction "GND_D29") (pintype "power_in"))
      (node (ref "SENSOR") (pin "E15") (pinfunction "GND_E15") (pintype "power_in"))
      (node (ref "SENSOR") (pin "E16") (pinfunction "GND_E16") (pintype "power_in"))
      (node (ref "SENSOR") (pin "E25") (pinfunction "GND_E25") (pintype "power_in"))
      (node (ref "SENSOR") (pin "E27") (pinfunction "GND_E27") (pintype "power_in"))
      (node (ref "SENSOR") (pin "E3") (pinfunction "GND_E3") (pintype "power_in"))
      (node (ref "SENSOR") (pin "E4") (pinfunction "DIO2_E4") (pintype "output"))
      (node (ref "SENSOR") (pin "F27") (pinfunction "GND_F27") (pintype "power_in"))
      (node (ref "SENSOR") (pin "F4") (pinfunction "DIO1_F4") (pintype "output"))
      (node (ref "SENSOR") (pin "G3") (pinfunction "DIO4_G3") (pintype "output"))
      (node (ref "SENSOR") (pin "G5") (pinfunction "GND_G5") (pintype "power_in"))
      (node (ref "SENSOR") (pin "H1") (pinfunction "GND_H1") (pintype "power_in"))
      (node (ref "SENSOR") (pin "H21") (pinfunction "GND_H21") (pintype "power_in"))
      (node (ref "SENSOR") (pin "H25") (pinfunction "GND_H25") (pintype "power_in"))
      (node (ref "SENSOR") (pin "H27") (pinfunction "GND_H27") (pintype "power_in"))
      (node (ref "SENSOR") (pin "H4") (pinfunction "DIO3_H4") (pintype "output"))
      (node (ref "SENSOR") (pin "H6") (pinfunction "GND_H6") (pintype "power_in"))
      (node (ref "SENSOR") (pin "H9") (pinfunction "GND_H9") (pintype "power_in"))
      (node (ref "U1") (pin "6") (pinfunction "ANODE_6") (pintype "input"))
      (node (ref "U2") (pin "6") (pinfunction "ANODE_6") (pintype "input"))
      (node (ref "U3") (pin "2") (pinfunction "GND_2") (pintype "power_in"))
      (node (ref "U3") (pin "EP") (pinfunction "EP_EP") (pintype "power_in"))
      (node (ref "U4") (pin "16") (pinfunction "DIR2_16") (pintype "input"))
      (node (ref "U4") (pin "7") (pinfunction "~{OE}_7") (pintype "input"))
      (node (ref "U4") (pin "8") (pinfunction "GND_8") (pintype "passive"))
      (node (ref "U5") (pin "6") (pinfunction "DIR4_6") (pintype "input"))
      (node (ref "U5") (pin "7") (pinfunction "~{OE}_7") (pintype "input"))
      (node (ref "U5") (pin "8") (pinfunction "GND_8") (pintype "passive"))
      (node (ref "U6") (pin "16") (pinfunction "DIR2_16") (pintype "input"))
      (node (ref "U6") (pin "7") (pinfunction "~{OE}_7") (pintype "input"))
      (node (ref "U6") (pin "8") (pinfunction "GND_8") (pintype "passive"))
      (node (ref "U7") (pin "4") (pinfunction "GND_4") (pintype "power_in"))
      (node (ref "U7") (pin "5") (pinfunction "A2_5") (pintype "input"))
      (node (ref "U7") (pin "6") (pinfunction "A1_6") (pintype "input"))
      (node (ref "U7") (pin "7") (pinfunction "A0_7") (pintype "input"))
      (node (ref "UEP") (pin "1") (pinfunction "A0_1") (pintype "input"))
      (node (ref "UEP") (pin "2") (pinfunction "A1_2") (pintype "input"))
      (node (ref "UEP") (pin "3") (pinfunction "A2_3") (pintype "input"))
      (node (ref "UEP") (pin "4") (pinfunction "GND_4") (pintype "passive"))
      (node (ref "UEP") (pin "EP") (pinfunction "EP_EP") (pintype "passive"))
      (node (ref "UNE") (pin "4") (pinfunction "VSS_4") (pintype "power_in"))
      (node (ref "UNE") (pin "EP") (pinfunction "EP_EP") (pintype "passive"))
      (node (ref "UNN") (pin "4") (pinfunction "VSS_4") (pintype "power_in"))
      (node (ref "UNN") (pin "EP") (pinfunction "EP_EP") (pintype "passive"))
      (node (ref "UNW") (pin "4") (pinfunction "VSS_4") (pintype "power_in"))
      (node (ref "UNW") (pin "EP") (pinfunction "EP_EP") (pintype "passive"))
      (node (ref "USE") (pin "4") (pinfunction "VSS_4") (pintype "power_in"))
      (node (ref "USE") (pin "EP") (pinfunction "EP_EP") (pintype "passive"))
      (node (ref "USS") (pin "4") (pinfunction "VSS_4") (pintype "power_in"))
      (node (ref "USS") (pin "EP") (pinfunction "EP_EP") (pintype "passive"))
      (node (ref "USW") (pin "4") (pinfunction "VSS_4") (pintype "power_in"))
      (node (ref "USW") (pin "EP") (pinfunction "EP_EP") (pintype "passive"))
      (node (ref "X-NORTH") (pin "102") (pinfunction "102_102") (pintype "bidirectional"))
      (node (ref "X-NORTH") (pin "103") (pinfunction "103_103") (pintype "bidirectional"))
      (node (ref "X-NORTH") (pin "108") (pinfunction "108_108") (pintype "bidirectional"))
      (node (ref "X-NORTH") (pin "114") (pinfunction "114_114") (pintype "bidirectional"))
      (node (ref "X-NORTH") (pin "12") (pinfunction "12_12") (pintype "bidirectional"))
      (node (ref "X-NORTH") (pin "120") (pinfunction "120_120") (pintype "bidirectional"))
      (node (ref "X-NORTH") (pin "126") (pinfunction "126_126") (pintype "bidirectional"))
      (node (ref "X-NORTH") (pin "132") (pinfunction "132_132") (pintype "bidirectional"))
      (node (ref "X-NORTH") (pin "138") (pinfunction "138_138") (pintype "bidirectional"))
      (node (ref "X-NORTH") (pin "139") (pinfunction "139_139") (pintype "bidirectional"))
      (node (ref "X-NORTH") (pin "18") (pinfunction "18_18") (pintype "bidirectional"))
      (node (ref "X-NORTH") (pin "24") (pinfunction "24_24") (pintype "bidirectional"))
      (node (ref "X-NORTH") (pin "30") (pinfunction "30_30") (pintype "bidirectional"))
      (node (ref "X-NORTH") (pin "36") (pinfunction "36_36") (pintype "bidirectional"))
      (node (ref "X-NORTH") (pin "42") (pinfunction "42_42") (pintype "bidirectional"))
      (node (ref "X-NORTH") (pin "43") (pinfunction "43_43") (pintype "bidirectional"))
      (node (ref "X-NORTH") (pin "48") (pinfunction "48_48") (pintype "bidirectional"))
      (node (ref "X-NORTH") (pin "54") (pinfunction "54_54") (pintype "bidirectional"))
      (node (ref "X-NORTH") (pin "60") (pinfunction "60_60") (pintype "bidirectional"))
      (node (ref "X-NORTH") (pin "66") (pinfunction "66_66") (pintype "bidirectional"))
      (node (ref "X-NORTH") (pin "72") (pinfunction "72_72") (pintype "bidirectional"))
      (node (ref "X-NORTH") (pin "78") (pinfunction "78_78") (pintype "bidirectional"))
      (node (ref "X-NORTH") (pin "84") (pinfunction "84_84") (pintype "bidirectional"))
      (node (ref "X-NORTH") (pin "90") (pinfunction "90_90") (pintype "bidirectional"))
      (node (ref "X-NORTH") (pin "96") (pinfunction "96_96") (pintype "bidirectional"))
      (node (ref "X-SOUTH") (pin "102") (pinfunction "102_102") (pintype "bidirectional"))
      (node (ref "X-SOUTH") (pin "103") (pinfunction "103_103") (pintype "bidirectional"))
      (node (ref "X-SOUTH") (pin "108") (pinfunction "108_108") (pintype "bidirectional"))
      (node (ref "X-SOUTH") (pin "114") (pinfunction "114_114") (pintype "bidirectional"))
      (node (ref "X-SOUTH") (pin "12") (pinfunction "12_12") (pintype "bidirectional"))
      (node (ref "X-SOUTH") (pin "120") (pinfunction "120_120") (pintype "bidirectional"))
      (node (ref "X-SOUTH") (pin "126") (pinfunction "126_126") (pintype "bidirectional"))
      (node (ref "X-SOUTH") (pin "132") (pinfunction "132_132") (pintype "bidirectional"))
      (node (ref "X-SOUTH") (pin "138") (pinfunction "138_138") (pintype "bidirectional"))
      (node (ref "X-SOUTH") (pin "139") (pinfunction "139_139") (pintype "bidirectional"))
      (node (ref "X-SOUTH") (pin "18") (pinfunction "18_18") (pintype "bidirectional"))
      (node (ref "X-SOUTH") (pin "24") (pinfunction "24_24") (pintype "bidirectional"))
      (node (ref "X-SOUTH") (pin "30") (pinfunction "30_30") (pintype "bidirectional"))
      (node (ref "X-SOUTH") (pin "36") (pinfunction "36_36") (pintype "bidirectional"))
      (node (ref "X-SOUTH") (pin "42") (pinfunction "42_42") (pintype "bidirectional"))
      (node (ref "X-SOUTH") (pin "43") (pinfunction "43_43") (pintype "bidirectional"))
      (node (ref "X-SOUTH") (pin "48") (pinfunction "48_48") (pintype "bidirectional"))
      (node (ref "X-SOUTH") (pin "54") (pinfunction "54_54") (pintype "bidirectional"))
      (node (ref "X-SOUTH") (pin "60") (pinfunction "60_60") (pintype "bidirectional"))
      (node (ref "X-SOUTH") (pin "66") (pinfunction "66_66") (pintype "bidirectional"))
      (node (ref "X-SOUTH") (pin "72") (pinfunction "72_72") (pintype "bidirectional"))
      (node (ref "X-SOUTH") (pin "78") (pinfunction "78_78") (pintype "bidirectional"))
      (node (ref "X-SOUTH") (pin "84") (pinfunction "84_84") (pintype "bidirectional"))
      (node (ref "X-SOUTH") (pin "90") (pinfunction "90_90") (pintype "bidirectional"))
      (node (ref "X-SOUTH") (pin "96") (pinfunction "96_96") (pintype "bidirectional"))
    )
    (net (code "4") (name "N$42") (class "Default")
      (node (ref "SENSOR") (pin "A2") (pinfunction "TANA_A2") (pintype "output"))
    )
    (net (code "5") (name "N00_N") (class "Default")
      (node (ref "R25") (pin "2") (pinfunction "2_2") (pintype "passive"))
      (node (ref "SENSOR") (pin "E6") (pinfunction "LVDS_CLK_P_E6") (pintype "input"))
      (node (ref "X-NORTH") (pin "16") (pinfunction "16_16") (pintype "bidirectional"))
    )
    (net (code "6") (name "N00_P") (class "Default")
      (node (ref "R25") (pin "1") (pinfunction "1_1") (pintype "passive"))
      (node (ref "SENSOR") (pin "E5") (pinfunction "LVDS_CLK_N_E5") (pintype "input"))
      (node (ref "X-NORTH") (pin "14") (pinfunction "14_14") (pintype "bidirectional"))
    )
    (net (code "7") (name "N01_N") (class "Default")
      (node (ref "SENSOR") (pin "G7") (pinfunction "OUTCLK_P_G7") (pintype "output"))
      (node (ref "X-NORTH") (pin "17") (pinfunction "17_17") (pintype "bidirectional"))
    )
    (net (code "8") (name "N01_P") (class "Default")
      (node (ref "SENSOR") (pin "G6") (pinfunction "OUTCLK_N_G6") (pintype "output"))
      (node (ref "X-NORTH") (pin "15") (pinfunction "15_15") (pintype "bidirectional"))
    )
    (net (code "9") (name "N02_N") (class "Default")
      (node (ref "SENSOR") (pin "F7") (pinfunction "OUT33_P_F7") (pintype "output"))
      (node (ref "X-NORTH") (pin "22") (pinfunction "22_22") (pintype "bidirectional"))
    )
    (net (code "10") (name "N02_P") (class "Default")
      (node (ref "SENSOR") (pin "F6") (pinfunction "OUT33_N_F6") (pintype "output"))
      (node (ref "X-NORTH") (pin "20") (pinfunction "20_20") (pintype "bidirectional"))
    )
    (net (code "11") (name "N03_N") (class "Default")
      (node (ref "X-NORTH") (pin "23") (pinfunction "23_23") (pintype "bidirectional"))
    )
    (net (code "12") (name "N03_P") (class "Default")
      (node (ref "X-NORTH") (pin "21") (pinfunction "21_21") (pintype "bidirectional"))
    )
    (net (code "13") (name "N04_N") (class "Default")
      (node (ref "SENSOR") (pin "E8") (pinfunction "OUT35_P_E8") (pintype "output"))
      (node (ref "X-NORTH") (pin "28") (pinfunction "28_28") (pintype "bidirectional"))
    )
    (net (code "14") (name "N04_P") (class "Default")
      (node (ref "SENSOR") (pin "E7") (pinfunction "OUT35_N_E7") (pintype "output"))
      (node (ref "X-NORTH") (pin "26") (pinfunction "26_26") (pintype "bidirectional"))
    )
    (net (code "15") (name "N05_N") (class "Default")
      (node (ref "SENSOR") (pin "H8") (pinfunction "OUT34_P_H8") (pintype "output"))
      (node (ref "X-NORTH") (pin "29") (pinfunction "29_29") (pintype "bidirectional"))
    )
    (net (code "16") (name "N05_P") (class "Default")
      (node (ref "SENSOR") (pin "H7") (pinfunction "OUT34_N_H7") (pintype "output"))
      (node (ref "X-NORTH") (pin "27") (pinfunction "27_27") (pintype "bidirectional"))
    )
    (net (code "17") (name "N06_N") (class "Default")
      (node (ref "SENSOR") (pin "F9") (pinfunction "OUT37_P_F9") (pintype "output"))
      (node (ref "X-NORTH") (pin "34") (pinfunction "34_34") (pintype "bidirectional"))
    )
    (net (code "18") (name "N06_P") (class "Default")
      (node (ref "SENSOR") (pin "F8") (pinfunction "OUT37_N_F8") (pintype "output"))
      (node (ref "X-NORTH") (pin "32") (pinfunction "32_32") (pintype "bidirectional"))
    )
    (net (code "19") (name "N07_N") (class "Default")
      (node (ref "SENSOR") (pin "G9") (pinfunction "OUT36_P_G9") (pintype "output"))
      (node (ref "X-NORTH") (pin "35") (pinfunction "35_35") (pintype "bidirectional"))
    )
    (net (code "20") (name "N07_P") (class "Default")
      (node (ref "SENSOR") (pin "G8") (pinfunction "OUT36_N_G8") (pintype "output"))
      (node (ref "X-NORTH") (pin "33") (pinfunction "33_33") (pintype "bidirectional"))
    )
    (net (code "21") (name "N08_N") (class "Default")
      (node (ref "SENSOR") (pin "E10") (pinfunction "OUT38_P_E10") (pintype "output"))
      (node (ref "X-NORTH") (pin "40") (pinfunction "40_40") (pintype "bidirectional"))
    )
    (net (code "22") (name "N08_P") (class "Default")
      (node (ref "SENSOR") (pin "E9") (pinfunction "OUT38_N_E9") (pintype "output"))
      (node (ref "X-NORTH") (pin "38") (pinfunction "38_38") (pintype "bidirectional"))
    )
    (net (code "23") (name "N09_N") (class "Default")
      (node (ref "SENSOR") (pin "G11") (pinfunction "OUT39_P_G11") (pintype "output"))
      (node (ref "X-NORTH") (pin "41") (pinfunction "41_41") (pintype "bidirectional"))
    )
    (net (code "24") (name "N09_P") (class "Default")
      (node (ref "SENSOR") (pin "G10") (pinfunction "OUT39_N_G10") (pintype "output"))
      (node (ref "X-NORTH") (pin "39") (pinfunction "39_39") (pintype "bidirectional"))
    )
    (net (code "25") (name "N10_N") (class "Default")
      (node (ref "SENSOR") (pin "F11") (pinfunction "OUT40_P_F11") (pintype "output"))
      (node (ref "X-NORTH") (pin "46") (pinfunction "46_46") (pintype "bidirectional"))
    )
    (net (code "26") (name "N10_P") (class "Default")
      (node (ref "SENSOR") (pin "F10") (pinfunction "OUT40_N_F10") (pintype "output"))
      (node (ref "X-NORTH") (pin "44") (pinfunction "44_44") (pintype "bidirectional"))
    )
    (net (code "27") (name "N11_N") (class "Default")
      (node (ref "SENSOR") (pin "H12") (pinfunction "OUT41_P_H12") (pintype "output"))
      (node (ref "X-NORTH") (pin "47") (pinfunction "47_47") (pintype "bidirectional"))
    )
    (net (code "28") (name "N11_P") (class "Default")
      (node (ref "SENSOR") (pin "H11") (pinfunction "OUT41_N_H11") (pintype "output"))
      (node (ref "X-NORTH") (pin "45") (pinfunction "45_45") (pintype "bidirectional"))
    )
    (net (code "29") (name "N12_N") (class "Default")
      (node (ref "SENSOR") (pin "E12") (pinfunction "OUT42_P_E12") (pintype "output"))
      (node (ref "X-NORTH") (pin "52") (pinfunction "52_52") (pintype "bidirectional"))
    )
    (net (code "30") (name "N12_P") (class "Default")
      (node (ref "SENSOR") (pin "E11") (pinfunction "OUT42_N_E11") (pintype "output"))
      (node (ref "X-NORTH") (pin "50") (pinfunction "50_50") (pintype "bidirectional"))
    )
    (net (code "31") (name "N13_N") (class "Default")
      (node (ref "SENSOR") (pin "G13") (pinfunction "OUT43_P_G13") (pintype "output"))
      (node (ref "X-NORTH") (pin "53") (pinfunction "53_53") (pintype "bidirectional"))
    )
    (net (code "32") (name "N13_P") (class "Default")
      (node (ref "SENSOR") (pin "G12") (pinfunction "OUT43_N_G12") (pintype "output"))
      (node (ref "X-NORTH") (pin "51") (pinfunction "51_51") (pintype "bidirectional"))
    )
    (net (code "33") (name "N14_N") (class "Default")
      (node (ref "SENSOR") (pin "F13") (pinfunction "OUT44_P_F13") (pintype "output"))
      (node (ref "X-NORTH") (pin "58") (pinfunction "58_58") (pintype "bidirectional"))
    )
    (net (code "34") (name "N14_P") (class "Default")
      (node (ref "SENSOR") (pin "F12") (pinfunction "OUT44_N_F12") (pintype "output"))
      (node (ref "X-NORTH") (pin "56") (pinfunction "56_56") (pintype "bidirectional"))
    )
    (net (code "35") (name "N15_N") (class "Default")
      (node (ref "SENSOR") (pin "H14") (pinfunction "OUT45_P_H14") (pintype "output"))
      (node (ref "X-NORTH") (pin "59") (pinfunction "59_59") (pintype "bidirectional"))
    )
    (net (code "36") (name "N15_P") (class "Default")
      (node (ref "SENSOR") (pin "H13") (pinfunction "OUT45_N_H13") (pintype "output"))
      (node (ref "X-NORTH") (pin "57") (pinfunction "57_57") (pintype "bidirectional"))
    )
    (net (code "37") (name "N16_N") (class "Default")
      (node (ref "SENSOR") (pin "E14") (pinfunction "OUT46_P_E14") (pintype "output"))
      (node (ref "X-NORTH") (pin "64") (pinfunction "64_64") (pintype "bidirectional"))
    )
    (net (code "38") (name "N16_P") (class "Default")
      (node (ref "SENSOR") (pin "E13") (pinfunction "OUT46_N_E13") (pintype "output"))
      (node (ref "X-NORTH") (pin "62") (pinfunction "62_62") (pintype "bidirectional"))
    )
    (net (code "39") (name "N17_N") (class "Default")
      (node (ref "SENSOR") (pin "G15") (pinfunction "OUT47_P_G15") (pintype "output"))
      (node (ref "X-NORTH") (pin "65") (pinfunction "65_65") (pintype "bidirectional"))
    )
    (net (code "40") (name "N17_P") (class "Default")
      (node (ref "SENSOR") (pin "G14") (pinfunction "OUT47_N_G14") (pintype "output"))
      (node (ref "X-NORTH") (pin "63") (pinfunction "63_63") (pintype "bidirectional"))
    )
    (net (code "41") (name "N18_N") (class "Default")
      (node (ref "SENSOR") (pin "F15") (pinfunction "OUT48_P_F15") (pintype "output"))
      (node (ref "X-NORTH") (pin "70") (pinfunction "70_70") (pintype "bidirectional"))
    )
    (net (code "42") (name "N18_P") (class "Default")
      (node (ref "SENSOR") (pin "F14") (pinfunction "OUT48_N_F14") (pintype "output"))
      (node (ref "X-NORTH") (pin "68") (pinfunction "68_68") (pintype "bidirectional"))
    )
    (net (code "43") (name "N19_N") (class "Default")
      (node (ref "SENSOR") (pin "G17") (pinfunction "OUT50_P_G17") (pintype "output"))
      (node (ref "X-NORTH") (pin "71") (pinfunction "71_71") (pintype "bidirectional"))
    )
    (net (code "44") (name "N19_P") (class "Default")
      (node (ref "SENSOR") (pin "G16") (pinfunction "OUT50_N_G16") (pintype "output"))
      (node (ref "X-NORTH") (pin "69") (pinfunction "69_69") (pintype "bidirectional"))
    )
    (net (code "45") (name "N20_N") (class "Default")
      (node (ref "SENSOR") (pin "F17") (pinfunction "OUT49_P_F17") (pintype "output"))
      (node (ref "X-NORTH") (pin "76") (pinfunction "76_76") (pintype "bidirectional"))
    )
    (net (code "46") (name "N20_P") (class "Default")
      (node (ref "SENSOR") (pin "F16") (pinfunction "OUT49_N_F16") (pintype "output"))
      (node (ref "X-NORTH") (pin "74") (pinfunction "74_74") (pintype "bidirectional"))
    )
    (net (code "47") (name "N21_N") (class "Default")
      (node (ref "SENSOR") (pin "H18") (pinfunction "OUT52_P_H18") (pintype "output"))
      (node (ref "X-NORTH") (pin "77") (pinfunction "77_77") (pintype "bidirectional"))
    )
    (net (code "48") (name "N21_P") (class "Default")
      (node (ref "SENSOR") (pin "H17") (pinfunction "OUT52_N_H17") (pintype "output"))
      (node (ref "X-NORTH") (pin "75") (pinfunction "75_75") (pintype "bidirectional"))
    )
    (net (code "49") (name "N22_N") (class "Default")
      (node (ref "SENSOR") (pin "E18") (pinfunction "OUT51_P_E18") (pintype "output"))
      (node (ref "X-NORTH") (pin "82") (pinfunction "82_82") (pintype "bidirectional"))
    )
    (net (code "50") (name "N22_P") (class "Default")
      (node (ref "SENSOR") (pin "E17") (pinfunction "OUT51_N_E17") (pintype "output"))
      (node (ref "X-NORTH") (pin "80") (pinfunction "80_80") (pintype "bidirectional"))
    )
    (net (code "51") (name "N23_N") (class "Default")
      (node (ref "SENSOR") (pin "G19") (pinfunction "OUT54_P_G19") (pintype "output"))
      (node (ref "X-NORTH") (pin "83") (pinfunction "83_83") (pintype "bidirectional"))
    )
    (net (code "52") (name "N23_P") (class "Default")
      (node (ref "SENSOR") (pin "G18") (pinfunction "OUT54_N_G18") (pintype "output"))
      (node (ref "X-NORTH") (pin "81") (pinfunction "81_81") (pintype "bidirectional"))
    )
    (net (code "53") (name "N24_N") (class "Default")
      (node (ref "SENSOR") (pin "F19") (pinfunction "OUT53_P_F19") (pintype "output"))
      (node (ref "X-NORTH") (pin "88") (pinfunction "88_88") (pintype "bidirectional"))
    )
    (net (code "54") (name "N24_P") (class "Default")
      (node (ref "SENSOR") (pin "F18") (pinfunction "OUT53_N_F18") (pintype "output"))
      (node (ref "X-NORTH") (pin "86") (pinfunction "86_86") (pintype "bidirectional"))
    )
    (net (code "55") (name "N25_N") (class "Default")
      (node (ref "SENSOR") (pin "H20") (pinfunction "OUT56_P_H20") (pintype "output"))
      (node (ref "X-NORTH") (pin "89") (pinfunction "89_89") (pintype "bidirectional"))
    )
    (net (code "56") (name "N25_P") (class "Default")
      (node (ref "SENSOR") (pin "H19") (pinfunction "OUT56_N_H19") (pintype "output"))
      (node (ref "X-NORTH") (pin "87") (pinfunction "87_87") (pintype "bidirectional"))
    )
    (net (code "57") (name "N26_N") (class "Default")
      (node (ref "SENSOR") (pin "E20") (pinfunction "OUT55_P_E20") (pintype "output"))
      (node (ref "X-NORTH") (pin "94") (pinfunction "94_94") (pintype "bidirectional"))
    )
    (net (code "58") (name "N26_P") (class "Default")
      (node (ref "SENSOR") (pin "E19") (pinfunction "OUT55_N_E19") (pintype "output"))
      (node (ref "X-NORTH") (pin "92") (pinfunction "92_92") (pintype "bidirectional"))
    )
    (net (code "59") (name "N27_N") (class "Default")
      (node (ref "SENSOR") (pin "G21") (pinfunction "OUT58_P_G21") (pintype "output"))
      (node (ref "X-NORTH") (pin "95") (pinfunction "95_95") (pintype "bidirectional"))
    )
    (net (code "60") (name "N27_P") (class "Default")
      (node (ref "SENSOR") (pin "G20") (pinfunction "OUT58_N_G20") (pintype "output"))
      (node (ref "X-NORTH") (pin "93") (pinfunction "93_93") (pintype "bidirectional"))
    )
    (net (code "61") (name "N28_N") (class "Default")
      (node (ref "SENSOR") (pin "F21") (pinfunction "OUT57_P_F21") (pintype "output"))
      (node (ref "X-NORTH") (pin "100") (pinfunction "100_100") (pintype "bidirectional"))
    )
    (net (code "62") (name "N28_P") (class "Default")
      (node (ref "SENSOR") (pin "F20") (pinfunction "OUT57_N_F20") (pintype "output"))
      (node (ref "X-NORTH") (pin "98") (pinfunction "98_98") (pintype "bidirectional"))
    )
    (net (code "63") (name "N29_N") (class "Default")
      (node (ref "SENSOR") (pin "G23") (pinfunction "OUT61_P_G23") (pintype "output"))
      (node (ref "X-NORTH") (pin "101") (pinfunction "101_101") (pintype "bidirectional"))
    )
    (net (code "64") (name "N29_P") (class "Default")
      (node (ref "SENSOR") (pin "G22") (pinfunction "OUT61_N_G22") (pintype "output"))
      (node (ref "X-NORTH") (pin "99") (pinfunction "99_99") (pintype "bidirectional"))
    )
    (net (code "65") (name "N30_N") (class "Default")
      (node (ref "SENSOR") (pin "E22") (pinfunction "OUT59_P_E22") (pintype "output"))
      (node (ref "X-NORTH") (pin "106") (pinfunction "106_106") (pintype "bidirectional"))
    )
    (net (code "66") (name "N30_P") (class "Default")
      (node (ref "SENSOR") (pin "E21") (pinfunction "OUT59_N_E21") (pintype "output"))
      (node (ref "X-NORTH") (pin "104") (pinfunction "104_104") (pintype "bidirectional"))
    )
    (net (code "67") (name "N31_N") (class "Default")
      (node (ref "SENSOR") (pin "H24") (pinfunction "OUT63_P_H24") (pintype "output"))
      (node (ref "X-NORTH") (pin "107") (pinfunction "107_107") (pintype "bidirectional"))
    )
    (net (code "68") (name "N31_P") (class "Default")
      (node (ref "SENSOR") (pin "H23") (pinfunction "OUT63_N_H23") (pintype "output"))
      (node (ref "X-NORTH") (pin "105") (pinfunction "105_105") (pintype "bidirectional"))
    )
    (net (code "69") (name "N32_N") (class "Default")
      (node (ref "SENSOR") (pin "F23") (pinfunction "OUT60_P_F23") (pintype "output"))
      (node (ref "X-NORTH") (pin "112") (pinfunction "112_112") (pintype "bidirectional"))
    )
    (net (code "70") (name "N32_P") (class "Default")
      (node (ref "SENSOR") (pin "F22") (pinfunction "OUT60_N_F22") (pintype "output"))
      (node (ref "X-NORTH") (pin "110") (pinfunction "110_110") (pintype "bidirectional"))
    )
    (net (code "71") (name "N33_N") (class "Default")
      (node (ref "SENSOR") (pin "G25") (pinfunction "OUT64_P_G25") (pintype "output"))
      (node (ref "X-NORTH") (pin "113") (pinfunction "113_113") (pintype "bidirectional"))
    )
    (net (code "72") (name "N33_P") (class "Default")
      (node (ref "SENSOR") (pin "G24") (pinfunction "OUT64_N_G24") (pintype "output"))
      (node (ref "X-NORTH") (pin "111") (pinfunction "111_111") (pintype "bidirectional"))
    )
    (net (code "73") (name "N34_N") (class "Default")
      (node (ref "SENSOR") (pin "E24") (pinfunction "OUT62_P_E24") (pintype "output"))
      (node (ref "X-NORTH") (pin "118") (pinfunction "118_118") (pintype "bidirectional"))
    )
    (net (code "74") (name "N34_P") (class "Default")
      (node (ref "SENSOR") (pin "E23") (pinfunction "OUT62_N_E23") (pintype "output"))
      (node (ref "X-NORTH") (pin "116") (pinfunction "116_116") (pintype "bidirectional"))
    )
    (net (code "75") (name "N35_N") (class "Default")
      (node (ref "U6") (pin "4") (pinfunction "A4_4") (pintype "bidirectional"))
      (node (ref "X-NORTH") (pin "119") (pinfunction "119_119") (pintype "bidirectional"))
    )
    (net (code "76") (name "N35_P") (class "Default")
      (node (ref "U6") (pin "3") (pinfunction "A3_3") (pintype "bidirectional"))
      (node (ref "X-NORTH") (pin "117") (pinfunction "117_117") (pintype "bidirectional"))
    )
    (net (code "77") (name "N36_N") (class "Default")
      (node (ref "X-NORTH") (pin "124") (pinfunction "124_124") (pintype "bidirectional"))
    )
    (net (code "78") (name "N36_P") (class "Default")
      (node (ref "X-NORTH") (pin "122") (pinfunction "122_122") (pintype "bidirectional"))
    )
    (net (code "79") (name "N37_N") (class "Default")
      (node (ref "U5") (pin "3") (pinfunction "A3_3") (pintype "bidirectional"))
      (node (ref "X-NORTH") (pin "125") (pinfunction "125_125") (pintype "bidirectional"))
    )
    (net (code "80") (name "N37_P") (class "Default")
      (node (ref "U5") (pin "4") (pinfunction "A4_4") (pintype "bidirectional"))
      (node (ref "X-NORTH") (pin "123") (pinfunction "123_123") (pintype "bidirectional"))
    )
    (net (code "81") (name "N38_N") (class "Default")
      (node (ref "U6") (pin "2") (pinfunction "A2_2") (pintype "bidirectional"))
      (node (ref "X-NORTH") (pin "130") (pinfunction "130_130") (pintype "bidirectional"))
    )
    (net (code "82") (name "N38_P") (class "Default")
      (node (ref "U6") (pin "1") (pinfunction "A1_1") (pintype "bidirectional"))
      (node (ref "X-NORTH") (pin "128") (pinfunction "128_128") (pintype "bidirectional"))
    )
    (net (code "83") (name "N39_N") (class "Default")
      (node (ref "U5") (pin "1") (pinfunction "A1_1") (pintype "bidirectional"))
      (node (ref "X-NORTH") (pin "131") (pinfunction "131_131") (pintype "bidirectional"))
    )
    (net (code "84") (name "N39_P") (class "Default")
      (node (ref "U5") (pin "2") (pinfunction "A2_2") (pintype "bidirectional"))
      (node (ref "X-NORTH") (pin "129") (pinfunction "129_129") (pintype "bidirectional"))
    )
    (net (code "85") (name "N_CHK_EN") (class "Default")
      (node (ref "X-NORTH") (pin "8") (pinfunction "8_8") (pintype "bidirectional"))
    )
    (net (code "86") (name "N_CHK_V") (class "Default")
      (node (ref "C2") (pin "1") (pinfunction "1_1") (pintype "passive"))
      (node (ref "C3") (pin "1") (pinfunction "1_1") (pintype "passive"))
      (node (ref "C4") (pin "1") (pinfunction "1_1") (pintype "passive"))
      (node (ref "R19") (pin "1") (pinfunction "1_1") (pintype "passive"))
      (node (ref "TP1") (pin "TP") (pinfunction "TP_TP") (pintype "input"))
      (node (ref "UNE") (pin "8") (pinfunction "VDD_8") (pintype "power_in"))
      (node (ref "UNN") (pin "8") (pinfunction "VDD_8") (pintype "power_in"))
      (node (ref "UNW") (pin "8") (pinfunction "VDD_8") (pintype "power_in"))
      (node (ref "X-NORTH") (pin "10") (pinfunction "10_10") (pintype "bidirectional"))
    )
    (net (code "87") (name "N_I2C_EN") (class "Default")
      (node (ref "X-NORTH") (pin "137") (pinfunction "137_137") (pintype "bidirectional"))
    )
    (net (code "88") (name "N_I2C_V") (class "Default")
      (node (ref "C1") (pin "1") (pinfunction "1_1") (pintype "passive"))
      (node (ref "R1X") (pin "1") (pinfunction "1_1") (pintype "passive"))
      (node (ref "UEP") (pin "8") (pinfunction "VCC_8") (pintype "power_in"))
      (node (ref "X-NORTH") (pin "135") (pinfunction "135_135") (pintype "bidirectional"))
    )
    (net (code "89") (name "N_REF") (class "Default")
      (node (ref "R19") (pin "2") (pinfunction "2_2") (pintype "passive"))
      (node (ref "TP2") (pin "TP") (pinfunction "TP_TP") (pintype "input"))
      (node (ref "U1") (pin "1") (pinfunction "CATHODE_1") (pintype "output"))
      (node (ref "U1") (pin "3") (pinfunction "REF_3") (pintype "input"))
      (node (ref "UNE") (pin "2") (pinfunction "VINA-_2") (pintype "input"))
      (node (ref "UNE") (pin "5") (pinfunction "VINB+_5") (pintype "input"))
      (node (ref "UNN") (pin "2") (pinfunction "VINA-_2") (pintype "input"))
      (node (ref "UNN") (pin "5") (pinfunction "VINB+_5") (pintype "input"))
      (node (ref "UNW") (pin "2") (pinfunction "VINA-_2") (pintype "input"))
      (node (ref "UNW") (pin "5") (pinfunction "VINB+_5") (pintype "input"))
    )
    (net (code "90") (name "N_SCK") (class "Default")
      (node (ref "U4") (pin "4") (pinfunction "A4_4") (pintype "bidirectional"))
      (node (ref "X-NORTH") (pin "144") (pinfunction "144_144") (pintype "bidirectional"))
    )
    (net (code "91") (name "N_SCL") (class "Default")
      (node (ref "UEP") (pin "6") (pinfunction "SCL_6") (pintype "input"))
      (node (ref "X-NORTH") (pin "143") (pinfunction "143_143") (pintype "bidirectional"))
    )
    (net (code "92") (name "N_SDA") (class "Default")
      (node (ref "UEP") (pin "5") (pinfunction "SDA_5") (pintype "bidirectional"))
      (node (ref "X-NORTH") (pin "141") (pinfunction "141_141") (pintype "bidirectional"))
    )
    (net (code "93") (name "N_SDI") (class "Default")
      (node (ref "U4") (pin "2") (pinfunction "A2_2") (pintype "bidirectional"))
      (node (ref "X-NORTH") (pin "140") (pinfunction "140_140") (pintype "bidirectional"))
    )
    (net (code "94") (name "N_SDO") (class "Default")
      (node (ref "U4") (pin "3") (pinfunction "A3_3") (pintype "bidirectional"))
      (node (ref "X-NORTH") (pin "142") (pinfunction "142_142") (pintype "bidirectional"))
    )
    (net (code "95") (name "N_SPI_EN") (class "Default")
      (node (ref "U4") (pin "1") (pinfunction "A1_1") (pintype "bidirectional"))
      (node (ref "X-NORTH") (pin "136") (pinfunction "136_136") (pintype "bidirectional"))
    )
    (net (code "96") (name "N_SPI_V") (class "Default")
      (node (ref "C59") (pin "1") (pinfunction "1_1") (pintype "passive"))
      (node (ref "U4") (pin "14") (pinfunction "VCCA_14") (pintype "power_in"))
      (node (ref "U4") (pin "15") (pinfunction "DIR1_15") (pintype "input"))
      (node (ref "U4") (pin "5") (pinfunction "DIR3_5") (pintype "input"))
      (node (ref "U4") (pin "6") (pinfunction "DIR4_6") (pintype "input"))
      (node (ref "X-NORTH") (pin "134") (pinfunction "134_134") (pintype "bidirectional"))
    )
    (net (code "97") (name "N_VE") (class "Default")
      (node (ref "C22") (pin "1") (pinfunction "1_1") (pintype "passive"))
      (node (ref "C23") (pin "1") (pinfunction "1_1") (pintype "passive"))
      (node (ref "C24") (pin "1") (pinfunction "1_1") (pintype "passive"))
      (node (ref "C25") (pin "1") (pinfunction "1_1") (pintype "passive"))
      (node (ref "C26") (pin "1") (pinfunction "1_1") (pintype "passive"))
      (node (ref "C27") (pin "1") (pinfunction "1_1") (pintype "passive"))
      (node (ref "C28") (pin "1") (pinfunction "1_1") (pintype "passive"))
      (node (ref "C50") (pin "1") (pinfunction "1_1") (pintype "passive"))
      (node (ref "C51") (pin "1") (pinfunction "1_1") (pintype "passive"))
      (node (ref "C52") (pin "1") (pinfunction "1_1") (pintype "passive"))
      (node (ref "C53") (pin "1") (pinfunction "1_1") (pintype "passive"))
      (node (ref "C54") (pin "1") (pinfunction "1_1") (pintype "passive"))
      (node (ref "C55") (pin "1") (pinfunction "1_1") (pintype "passive"))
      (node (ref "C56") (pin "1") (pinfunction "1_1") (pintype "passive"))
      (node (ref "C67") (pin "1") (pinfunction "1_1") (pintype "passive"))
      (node (ref "C69") (pin "1") (pinfunction "1_1") (pintype "passive"))
      (node (ref "C75") (pin "1") (pinfunction "1_1") (pintype "passive"))
      (node (ref "C76") (pin "1") (pinfunction "1_1") (pintype "passive"))
      (node (ref "C77") (pin "1") (pinfunction "1_1") (pintype "passive"))
      (node (ref "C84") (pin "1") (pinfunction "1_1") (pintype "passive"))
      (node (ref "C85") (pin "1") (pinfunction "1_1") (pintype "passive"))
      (node (ref "C86") (pin "1") (pinfunction "1_1") (pintype "passive"))
      (node (ref "C93") (pin "1") (pinfunction "1_1") (pintype "passive"))
      (node (ref "SENSOR") (pin "C26") (pinfunction "VDD33_C26") (pintype "power_in"))
      (node (ref "SENSOR") (pin "C27") (pinfunction "VDD33_C27") (pintype "power_in"))
      (node (ref "SENSOR") (pin "D26") (pinfunction "VDD33_D26") (pintype "power_in"))
      (node (ref "SENSOR") (pin "D3") (pinfunction "VDD33_D3") (pintype "power_in"))
      (node (ref "SENSOR") (pin "E26") (pinfunction "VDD33_E26") (pintype "power_in"))
      (node (ref "SENSOR") (pin "F26") (pinfunction "VDD33_F26") (pintype "power_in"))
      (node (ref "SENSOR") (pin "F5") (pinfunction "VDD33_F5") (pintype "power_in"))
      (node (ref "TP7") (pin "TP") (pinfunction "TP_TP") (pintype "input"))
      (node (ref "U4") (pin "13") (pinfunction "VCCB_13") (pintype "power_in"))
      (node (ref "U5") (pin "13") (pinfunction "VCCB_13") (pintype "power_in"))
      (node (ref "U6") (pin "13") (pinfunction "VCCB_13") (pintype "power_in"))
      (node (ref "X-NORTH") (pin "109") (pinfunction "109_109") (pintype "bidirectional"))
      (node (ref "X-NORTH") (pin "115") (pinfunction "115_115") (pintype "bidirectional"))
      (node (ref "X-NORTH") (pin "121") (pinfunction "121_121") (pintype "bidirectional"))
      (node (ref "X-NORTH") (pin "127") (pinfunction "127_127") (pintype "bidirectional"))
      (node (ref "X-NORTH") (pin "133") (pinfunction "133_133") (pintype "bidirectional"))
    )
    (net (code "98") (name "N_VE_CV") (class "Default")
      (node (ref "C10") (pin "1") (pinfunction "1_1") (pintype "passive"))
      (node (ref "R7") (pin "1") (pinfunction "1_1") (pintype "passive"))
      (node (ref "X-NORTH") (pin "6") (pinfunction "6_6") (pintype "bidirectional"))
    )
    (net (code "99") (name "N_VE_OV") (class "Default")
      (node (ref "UNE") (pin "7") (pinfunction "OUTB_7") (pintype "output"))
      (node (ref "X-NORTH") (pin "5") (pinfunction "5_5") (pintype "bidirectional"))
    )
    (net (code "100") (name "N_VE_UV") (class "Default")
      (node (ref "UNE") (pin "1") (pinfunction "OUTA_1") (pintype "output"))
      (node (ref "X-NORTH") (pin "11") (pinfunction "11_11") (pintype "bidirectional"))
    )
    (net (code "101") (name "N_VN") (class "Default")
      (node (ref "C31") (pin "1") (pinfunction "1_1") (pintype "passive"))
      (node (ref "C32") (pin "1") (pinfunction "1_1") (pintype "passive"))
      (node (ref "C33") (pin "1") (pinfunction "1_1") (pintype "passive"))
      (node (ref "C34") (pin "1") (pinfunction "1_1") (pintype "passive"))
      (node (ref "C35") (pin "1") (pinfunction "1_1") (pintype "passive"))
      (node (ref "C36") (pin "1") (pinfunction "1_1") (pintype "passive"))
      (node (ref "C37") (pin "1") (pinfunction "1_1") (pintype "passive"))
      (node (ref "C38") (pin "1") (pinfunction "1_1") (pintype "passive"))
      (node (ref "C39") (pin "1") (pinfunction "1_1") (pintype "passive"))
      (node (ref "C40") (pin "1") (pinfunction "1_1") (pintype "passive"))
      (node (ref "C41") (pin "1") (pinfunction "1_1") (pintype "passive"))
      (node (ref "C42") (pin "1") (pinfunction "1_1") (pintype "passive"))
      (node (ref "C43") (pin "1") (pinfunction "1_1") (pintype "passive"))
      (node (ref "C44") (pin "1") (pinfunction "1_1") (pintype "passive"))
      (node (ref "C68") (pin "1") (pinfunction "1_1") (pintype "passive"))
      (node (ref "C70") (pin "1") (pinfunction "1_1") (pintype "passive"))
      (node (ref "C78") (pin "1") (pinfunction "1_1") (pintype "passive"))
      (node (ref "C79") (pin "1") (pinfunction "1_1") (pintype "passive"))
      (node (ref "C80") (pin "1") (pinfunction "1_1") (pintype "passive"))
      (node (ref "C87") (pin "1") (pinfunction "1_1") (pintype "passive"))
      (node (ref "C88") (pin "1") (pinfunction "1_1") (pintype "passive"))
      (node (ref "C89") (pin "1") (pinfunction "1_1") (pintype "passive"))
      (node (ref "SENSOR") (pin "A10") (pinfunction "VDD18_A10") (pintype "power_in"))
      (node (ref "SENSOR") (pin "A15") (pinfunction "VDD18_A15") (pintype "power_in"))
      (node (ref "SENSOR") (pin "A16") (pinfunction "VDD18_A16") (pintype "power_in"))
      (node (ref "SENSOR") (pin "A22") (pinfunction "VDD18_A22") (pintype "power_in"))
      (node (ref "SENSOR") (pin "A26") (pinfunction "VDD18_A26") (pintype "power_in"))
      (node (ref "SENSOR") (pin "A27") (pinfunction "VDD18_A27") (pintype "power_in"))
      (node (ref "SENSOR") (pin "B4") (pinfunction "VDD18_B4") (pintype "power_in"))
      (node (ref "SENSOR") (pin "E1") (pinfunction "VDD18_PLL_E1") (pintype "power_in"))
      (node (ref "SENSOR") (pin "H10") (pinfunction "VDD18_H10") (pintype "power_in"))
      (node (ref "SENSOR") (pin "H15") (pinfunction "VDD18_H15") (pintype "power_in"))
      (node (ref "SENSOR") (pin "H16") (pinfunction "VDD18_H16") (pintype "power_in"))
      (node (ref "SENSOR") (pin "H22") (pinfunction "VDD18_H22") (pintype "power_in"))
      (node (ref "SENSOR") (pin "H26") (pinfunction "VDD18_H26") (pintype "power_in"))
      (node (ref "SENSOR") (pin "H5") (pinfunction "VDD18_H5") (pintype "power_in"))
      (node (ref "TP5") (pin "TP") (pinfunction "TP_TP") (pintype "input"))
      (node (ref "U5") (pin "14") (pinfunction "VCCA_14") (pintype "power_in"))
      (node (ref "U5") (pin "15") (pinfunction "DIR1_15") (pintype "input"))
      (node (ref "U5") (pin "16") (pinfunction "DIR2_16") (pintype "input"))
      (node (ref "U5") (pin "5") (pinfunction "DIR3_5") (pintype "input"))
      (node (ref "U6") (pin "14") (pinfunction "VCCA_14") (pintype "power_in"))
      (node (ref "U6") (pin "15") (pinfunction "DIR1_15") (pintype "input"))
      (node (ref "U6") (pin "5") (pinfunction "DIR3_5") (pintype "input"))
      (node (ref "U6") (pin "6") (pinfunction "DIR4_6") (pintype "input"))
      (node (ref "X-NORTH") (pin "49") (pinfunction "49_49") (pintype "bidirectional"))
      (node (ref "X-NORTH") (pin "55") (pinfunction "55_55") (pintype "bidirectional"))
      (node (ref "X-NORTH") (pin "61") (pinfunction "61_61") (pintype "bidirectional"))
      (node (ref "X-NORTH") (pin "67") (pinfunction "67_67") (pintype "bidirectional"))
      (node (ref "X-NORTH") (pin "73") (pinfunction "73_73") (pintype "bidirectional"))
      (node (ref "X-NORTH") (pin "79") (pinfunction "79_79") (pintype "bidirectional"))
      (node (ref "X-NORTH") (pin "85") (pinfunction "85_85") (pintype "bidirectional"))
      (node (ref "X-NORTH") (pin "91") (pinfunction "91_91") (pintype "bidirectional"))
      (node (ref "X-NORTH") (pin "97") (pinfunction "97_97") (pintype "bidirectional"))
    )
    (net (code "102") (name "N_VN_CV") (class "Default")
      (node (ref "C9") (pin "1") (pinfunction "1_1") (pintype "passive"))
      (node (ref "R4") (pin "1") (pinfunction "1_1") (pintype "passive"))
      (node (ref "X-NORTH") (pin "4") (pinfunction "4_4") (pintype "bidirectional"))
    )
    (net (code "103") (name "N_VN_OV") (class "Default")
      (node (ref "UNN") (pin "7") (pinfunction "OUTB_7") (pintype "output"))
      (node (ref "X-NORTH") (pin "3") (pinfunction "3_3") (pintype "bidirectional"))
    )
    (net (code "104") (name "N_VN_UV") (class "Default")
      (node (ref "UNN") (pin "1") (pinfunction "OUTA_1") (pintype "output"))
      (node (ref "X-NORTH") (pin "9") (pinfunction "9_9") (pintype "bidirectional"))
    )
    (net (code "105") (name "N_VW") (class "Default")
      (node (ref "C57") (pin "1") (pinfunction "1_1") (pintype "passive"))
      (node (ref "C58") (pin "1") (pinfunction "1_1") (pintype "passive"))
      (node (ref "C92") (pin "1") (pinfunction "1_1") (pintype "passive"))
      (node (ref "SENSOR") (pin "E2") (pinfunction "VDD_RES_E2") (pintype "power_in"))
      (node (ref "SENSOR") (pin "G4") (pinfunction "VDD_RES_G4") (pintype "power_in"))
      (node (ref "TP8") (pin "TP") (pinfunction "TP_TP") (pintype "input"))
      (node (ref "X-NORTH") (pin "13") (pinfunction "13_13") (pintype "bidirectional"))
      (node (ref "X-NORTH") (pin "19") (pinfunction "19_19") (pintype "bidirectional"))
      (node (ref "X-NORTH") (pin "25") (pinfunction "25_25") (pintype "bidirectional"))
      (node (ref "X-NORTH") (pin "31") (pinfunction "31_31") (pintype "bidirectional"))
      (node (ref "X-NORTH") (pin "37") (pinfunction "37_37") (pintype "bidirectional"))
    )
    (net (code "106") (name "N_VW_CV") (class "Default")
      (node (ref "C8") (pin "1") (pinfunction "1_1") (pintype "passive"))
      (node (ref "R1") (pin "1") (pinfunction "1_1") (pintype "passive"))
      (node (ref "X-NORTH") (pin "2") (pinfunction "2_2") (pintype "bidirectional"))
    )
    (net (code "107") (name "N_VW_OV") (class "Default")
      (node (ref "UNW") (pin "7") (pinfunction "OUTB_7") (pintype "output"))
      (node (ref "X-NORTH") (pin "1") (pinfunction "1_1") (pintype "bidirectional"))
    )
    (net (code "108") (name "N_VW_UV") (class "Default")
      (node (ref "UNW") (pin "1") (pinfunction "OUTA_1") (pintype "output"))
      (node (ref "X-NORTH") (pin "7") (pinfunction "7_7") (pintype "bidirectional"))
    )
    (net (code "109") (name "Net-(SENSORB-CMDN)") (class "Default")
      (node (ref "C61") (pin "1") (pinfunction "1_1") (pintype "passive"))
      (node (ref "SENSOR") (pin "F1") (pinfunction "CMDN_F1") (pintype "bidirectional"))
    )
    (net (code "110") (name "Net-(SENSORB-CMDP)") (class "Default")
      (node (ref "C22") (pin "2") (pinfunction "2_2") (pintype "passive"))
      (node (ref "SENSOR") (pin "F2") (pinfunction "CMDP_F2") (pintype "bidirectional"))
    )
    (net (code "111") (name "Net-(SENSORB-CMDP_COMP)") (class "Default")
      (node (ref "C28") (pin "2") (pinfunction "2_2") (pintype "passive"))
      (node (ref "SENSOR") (pin "H3") (pinfunction "CMDP_COMP_H3") (pintype "bidirectional"))
    )
    (net (code "112") (name "Net-(SENSORB-CMDP_COMP_INV)") (class "Default")
      (node (ref "C27") (pin "2") (pinfunction "2_2") (pintype "passive"))
      (node (ref "SENSOR") (pin "F3") (pinfunction "CMDP_COMP_INV_F3") (pintype "bidirectional"))
    )
    (net (code "113") (name "Net-(SENSORB-CMD_COLAMP)") (class "Default")
      (node (ref "C25") (pin "2") (pinfunction "2_2") (pintype "passive"))
      (node (ref "SENSOR") (pin "C6") (pinfunction "CMD_COLAMP_C6") (pintype "bidirectional"))
    )
    (net (code "114") (name "Net-(SENSORB-CMD_COL_LOAD)") (class "Default")
      (node (ref "C23") (pin "2") (pinfunction "2_2") (pintype "passive"))
      (node (ref "SENSOR") (pin "B1") (pinfunction "CMD_COL_LOAD_B1") (pintype "bidirectional"))
    )
    (net (code "115") (name "Net-(SENSORB-CMD_COL_PC)") (class "Default")
      (node (ref "C26") (pin "2") (pinfunction "2_2") (pintype "passive"))
      (node (ref "SENSOR") (pin "D1") (pinfunction "CMD_COL_PC_D1") (pintype "bidirectional"))
    )
    (net (code "116") (name "Net-(SENSORB-CMD_LVDS)") (class "Default")
      (node (ref "C62") (pin "1") (pinfunction "1_1") (pintype "passive"))
      (node (ref "SENSOR") (pin "C1") (pinfunction "CMD_LVDS_C1") (pintype "bidirectional"))
    )
    (net (code "117") (name "Net-(SENSORB-CMD_RAMP)") (class "Default")
      (node (ref "C24") (pin "2") (pinfunction "2_2") (pintype "passive"))
      (node (ref "SENSOR") (pin "B29") (pinfunction "CMD_RAMP_B29") (pintype "bidirectional"))
    )
    (net (code "118") (name "Net-(SENSORB-VBGAP)") (class "Default")
      (node (ref "C64") (pin "1") (pinfunction "1_1") (pintype "passive"))
      (node (ref "SENSOR") (pin "C29") (pinfunction "VBGAP_C29") (pintype "bidirectional"))
    )
    (net (code "119") (name "Net-(SENSORB-VCLAMP)") (class "Default")
      (node (ref "C63") (pin "1") (pinfunction "1_1") (pintype "passive"))
      (node (ref "SENSOR") (pin "D4") (pinfunction "VCLAMP_D4") (pintype "bidirectional"))
    )
    (net (code "120") (name "Net-(SENSORB-VCLAMP_ADC)") (class "Default")
      (node (ref "C60") (pin "1") (pinfunction "1_1") (pintype "passive"))
      (node (ref "SENSOR") (pin "G2") (pinfunction "VCLAMP_ADC_G2") (pintype "bidirectional"))
    )
    (net (code "121") (name "Net-(SENSORB-VPCH_H)") (class "Default")
      (node (ref "C71") (pin "1") (pinfunction "1_1") (pintype "passive"))
      (node (ref "SENSOR") (pin "C4") (pinfunction "VPCH_H_C4") (pintype "bidirectional"))
    )
    (net (code "122") (name "Net-(SENSORB-VPCH_L)") (class "Default")
      (node (ref "C14") (pin "1") (pinfunction "1_1") (pintype "passive"))
      (node (ref "SENSOR") (pin "A4") (pinfunction "VPCH_L_A4") (pintype "bidirectional"))
    )
    (net (code "123") (name "Net-(SENSORB-VREF)") (class "Default")
      (node (ref "C29") (pin "1") (pinfunction "1_1") (pintype "passive"))
      (node (ref "SENSOR") (pin "A3") (pinfunction "VREF_A3") (pintype "bidirectional"))
    )
    (net (code "124") (name "Net-(SENSORB-VREF_ADC)") (class "Default")
      (node (ref "C30") (pin "1") (pinfunction "1_1") (pintype "passive"))
      (node (ref "SENSOR") (pin "B3") (pinfunction "VREF_ADC_B3") (pintype "bidirectional"))
    )
    (net (code "125") (name "Net-(SENSORB-VRES_L)") (class "Default")
      (node (ref "C15") (pin "1") (pinfunction "1_1") (pintype "passive"))
      (node (ref "SENSOR") (pin "D5") (pinfunction "VRES_L_D5") (pintype "bidirectional"))
    )
    (net (code "126") (name "Net-(SENSORB-VTF_LOW0)") (class "Default")
      (node (ref "C18") (pin "1") (pinfunction "1_1") (pintype "passive"))
      (node (ref "SENSOR") (pin "C5") (pinfunction "VTF_LOW0_C5") (pintype "bidirectional"))
    )
    (net (code "127") (name "Net-(SENSORB-VTF_LOW1)") (class "Default")
      (node (ref "C19") (pin "1") (pinfunction "1_1") (pintype "passive"))
      (node (ref "SENSOR") (pin "D6") (pinfunction "VTF_LOW1_D6") (pintype "bidirectional"))
    )
    (net (code "128") (name "Net-(SENSORB-VTF_LOW2)") (class "Default")
      (node (ref "C20") (pin "1") (pinfunction "1_1") (pintype "passive"))
      (node (ref "SENSOR") (pin "B30") (pinfunction "VTF_LOW2_B30") (pintype "bidirectional"))
    )
    (net (code "129") (name "Net-(SENSORB-VTF_LOW3)") (class "Default")
      (node (ref "C21") (pin "1") (pinfunction "1_1") (pintype "passive"))
      (node (ref "SENSOR") (pin "C30") (pinfunction "VTF_LOW3_C30") (pintype "bidirectional"))
    )
    (net (code "130") (name "Net-(U3-ADJ)") (class "Default")
      (node (ref "R21") (pin "1") (pinfunction "1_1") (pintype "passive"))
      (node (ref "R22") (pin "2") (pinfunction "2_2") (pintype "passive"))
      (node (ref "U3") (pin "5") (pinfunction "ADJ_5") (pintype "input"))
    )
    (net (code "131") (name "Net-(U6-B4)") (class "Default")
      (node (ref "TP9") (pin "TP") (pinfunction "TP_TP") (pintype "input"))
      (node (ref "U6") (pin "9") (pinfunction "B4_9") (pintype "bidirectional"))
    )
    (net (code "132") (name "Net-(UEP-WP)") (class "Default")
      (node (ref "R1X") (pin "2") (pinfunction "2_2") (pintype "passive"))
      (node (ref "R2X") (pin "1") (pinfunction "1_1") (pintype "passive"))
      (node (ref "UEP") (pin "7") (pinfunction "WP_7") (pintype "input"))
    )
    (net (code "133") (name "Net-(UNE-VINA+)") (class "Default")
      (node (ref "R7") (pin "2") (pinfunction "2_2") (pintype "passive"))
      (node (ref "R8") (pin "1") (pinfunction "1_1") (pintype "passive"))
      (node (ref "UNE") (pin "3") (pinfunction "VINA+_3") (pintype "input"))
    )
    (net (code "134") (name "Net-(UNE-VINB-)") (class "Default")
      (node (ref "R8") (pin "2") (pinfunction "2_2") (pintype "passive"))
      (node (ref "R9") (pin "1") (pinfunction "1_1") (pintype "passive"))
      (node (ref "UNE") (pin "6") (pinfunction "VINB-_6") (pintype "input"))
    )
    (net (code "135") (name "Net-(UNN-VINA+)") (class "Default")
      (node (ref "R4") (pin "2") (pinfunction "2_2") (pintype "passive"))
      (node (ref "R5") (pin "1") (pinfunction "1_1") (pintype "passive"))
      (node (ref "UNN") (pin "3") (pinfunction "VINA+_3") (pintype "input"))
    )
    (net (code "136") (name "Net-(UNN-VINB-)") (class "Default")
      (node (ref "R5") (pin "2") (pinfunction "2_2") (pintype "passive"))
      (node (ref "R6") (pin "1") (pinfunction "1_1") (pintype "passive"))
      (node (ref "UNN") (pin "6") (pinfunction "VINB-_6") (pintype "input"))
    )
    (net (code "137") (name "Net-(UNW-VINA+)") (class "Default")
      (node (ref "R1") (pin "2") (pinfunction "2_2") (pintype "passive"))
      (node (ref "R2") (pin "1") (pinfunction "1_1") (pintype "passive"))
      (node (ref "UNW") (pin "3") (pinfunction "VINA+_3") (pintype "input"))
    )
    (net (code "138") (name "Net-(UNW-VINB-)") (class "Default")
      (node (ref "R2") (pin "2") (pinfunction "2_2") (pintype "passive"))
      (node (ref "R3") (pin "1") (pinfunction "1_1") (pintype "passive"))
      (node (ref "UNW") (pin "6") (pinfunction "VINB-_6") (pintype "input"))
    )
    (net (code "139") (name "Net-(USE-VINA+)") (class "Default")
      (node (ref "R10") (pin "2") (pinfunction "2_2") (pintype "passive"))
      (node (ref "R11") (pin "1") (pinfunction "1_1") (pintype "passive"))
      (node (ref "USE") (pin "3") (pinfunction "VINA+_3") (pintype "input"))
    )
    (net (code "140") (name "Net-(USE-VINB-)") (class "Default")
      (node (ref "R11") (pin "2") (pinfunction "2_2") (pintype "passive"))
      (node (ref "R12") (pin "1") (pinfunction "1_1") (pintype "passive"))
      (node (ref "USE") (pin "6") (pinfunction "VINB-_6") (pintype "input"))
    )
    (net (code "141") (name "Net-(USS-VINA+)") (class "Default")
      (node (ref "R13") (pin "2") (pinfunction "2_2") (pintype "passive"))
      (node (ref "R14") (pin "1") (pinfunction "1_1") (pintype "passive"))
      (node (ref "USS") (pin "3") (pinfunction "VINA+_3") (pintype "input"))
    )
    (net (code "142") (name "Net-(USS-VINB-)") (class "Default")
      (node (ref "R14") (pin "2") (pinfunction "2_2") (pintype "passive"))
      (node (ref "R15") (pin "1") (pinfunction "1_1") (pintype "passive"))
      (node (ref "USS") (pin "6") (pinfunction "VINB-_6") (pintype "input"))
    )
    (net (code "143") (name "Net-(USW-VINA+)") (class "Default")
      (node (ref "R16") (pin "2") (pinfunction "2_2") (pintype "passive"))
      (node (ref "R17") (pin "1") (pinfunction "1_1") (pintype "passive"))
      (node (ref "USW") (pin "3") (pinfunction "VINA+_3") (pintype "input"))
    )
    (net (code "144") (name "Net-(USW-VINB-)") (class "Default")
      (node (ref "R17") (pin "2") (pinfunction "2_2") (pintype "passive"))
      (node (ref "R18") (pin "1") (pinfunction "1_1") (pintype "passive"))
      (node (ref "USW") (pin "6") (pinfunction "VINB-_6") (pintype "input"))
    )
    (net (code "145") (name "S00_N") (class "Default")
      (node (ref "X-SOUTH") (pin "16") (pinfunction "16_16") (pintype "bidirectional"))
    )
    (net (code "146") (name "S00_P") (class "Default")
      (node (ref "X-SOUTH") (pin "14") (pinfunction "14_14") (pintype "bidirectional"))
    )
    (net (code "147") (name "S01_N") (class "Default")
      (node (ref "X-SOUTH") (pin "17") (pinfunction "17_17") (pintype "bidirectional"))
    )
    (net (code "148") (name "S01_P") (class "Default")
      (node (ref "X-SOUTH") (pin "15") (pinfunction "15_15") (pintype "bidirectional"))
    )
    (net (code "149") (name "S02_N") (class "Default")
      (node (ref "X-SOUTH") (pin "22") (pinfunction "22_22") (pintype "bidirectional"))
    )
    (net (code "150") (name "S02_P") (class "Default")
      (node (ref "X-SOUTH") (pin "20") (pinfunction "20_20") (pintype "bidirectional"))
    )
    (net (code "151") (name "S03_N") (class "Default")
      (node (ref "X-SOUTH") (pin "23") (pinfunction "23_23") (pintype "bidirectional"))
    )
    (net (code "152") (name "S03_P") (class "Default")
      (node (ref "X-SOUTH") (pin "21") (pinfunction "21_21") (pintype "bidirectional"))
    )
    (net (code "153") (name "S04_N") (class "Default")
      (node (ref "SENSOR") (pin "C24") (pinfunction "OUT32_N_C24") (pintype "output"))
      (node (ref "X-SOUTH") (pin "28") (pinfunction "28_28") (pintype "bidirectional"))
    )
    (net (code "154") (name "S04_P") (class "Default")
      (node (ref "SENSOR") (pin "C25") (pinfunction "OUT32_P_C25") (pintype "output"))
      (node (ref "X-SOUTH") (pin "26") (pinfunction "26_26") (pintype "bidirectional"))
    )
    (net (code "155") (name "S05_N") (class "Default")
      (node (ref "X-SOUTH") (pin "29") (pinfunction "29_29") (pintype "bidirectional"))
    )
    (net (code "156") (name "S05_P") (class "Default")
      (node (ref "X-SOUTH") (pin "27") (pinfunction "27_27") (pintype "bidirectional"))
    )
    (net (code "157") (name "S06_N") (class "Default")
      (node (ref "SENSOR") (pin "D23") (pinfunction "OUT30_N_D23") (pintype "output"))
      (node (ref "X-SOUTH") (pin "34") (pinfunction "34_34") (pintype "bidirectional"))
    )
    (net (code "158") (name "S06_P") (class "Default")
      (node (ref "SENSOR") (pin "D24") (pinfunction "OUT30_P_D24") (pintype "output"))
      (node (ref "X-SOUTH") (pin "32") (pinfunction "32_32") (pintype "bidirectional"))
    )
    (net (code "159") (name "S07_N") (class "Default")
      (node (ref "SENSOR") (pin "B24") (pinfunction "OUT31_N_B24") (pintype "output"))
      (node (ref "X-SOUTH") (pin "35") (pinfunction "35_35") (pintype "bidirectional"))
    )
    (net (code "160") (name "S07_P") (class "Default")
      (node (ref "SENSOR") (pin "B25") (pinfunction "OUT31_P_B25") (pintype "output"))
      (node (ref "X-SOUTH") (pin "33") (pinfunction "33_33") (pintype "bidirectional"))
    )
    (net (code "161") (name "S08_N") (class "Default")
      (node (ref "SENSOR") (pin "D21") (pinfunction "OUT27_N_D21") (pintype "output"))
      (node (ref "X-SOUTH") (pin "40") (pinfunction "40_40") (pintype "bidirectional"))
    )
    (net (code "162") (name "S08_P") (class "Default")
      (node (ref "SENSOR") (pin "D22") (pinfunction "OUT27_P_D22") (pintype "output"))
      (node (ref "X-SOUTH") (pin "38") (pinfunction "38_38") (pintype "bidirectional"))
    )
    (net (code "163") (name "S09_N") (class "Default")
      (node (ref "SENSOR") (pin "A23") (pinfunction "OUT29_N_A23") (pintype "output"))
      (node (ref "X-SOUTH") (pin "41") (pinfunction "41_41") (pintype "bidirectional"))
    )
    (net (code "164") (name "S09_P") (class "Default")
      (node (ref "SENSOR") (pin "A24") (pinfunction "OUT29_P_A24") (pintype "output"))
      (node (ref "X-SOUTH") (pin "39") (pinfunction "39_39") (pintype "bidirectional"))
    )
    (net (code "165") (name "S10_N") (class "Default")
      (node (ref "SENSOR") (pin "C21") (pinfunction "OUT28_N_C21") (pintype "output"))
      (node (ref "X-SOUTH") (pin "46") (pinfunction "46_46") (pintype "bidirectional"))
    )
    (net (code "166") (name "S10_P") (class "Default")
      (node (ref "SENSOR") (pin "C22") (pinfunction "OUT28_P_C22") (pintype "output"))
      (node (ref "X-SOUTH") (pin "44") (pinfunction "44_44") (pintype "bidirectional"))
    )
    (net (code "167") (name "S11_N") (class "Default")
      (node (ref "SENSOR") (pin "B20") (pinfunction "OUT26_N_B20") (pintype "output"))
      (node (ref "X-SOUTH") (pin "47") (pinfunction "47_47") (pintype "bidirectional"))
    )
    (net (code "168") (name "S11_P") (class "Default")
      (node (ref "SENSOR") (pin "B21") (pinfunction "OUT26_P_B21") (pintype "output"))
      (node (ref "X-SOUTH") (pin "45") (pinfunction "45_45") (pintype "bidirectional"))
    )
    (net (code "169") (name "S12_N") (class "Default")
      (node (ref "SENSOR") (pin "D19") (pinfunction "OUT24_N_D19") (pintype "output"))
      (node (ref "X-SOUTH") (pin "52") (pinfunction "52_52") (pintype "bidirectional"))
    )
    (net (code "170") (name "S12_P") (class "Default")
      (node (ref "SENSOR") (pin "D20") (pinfunction "OUT24_P_D20") (pintype "output"))
      (node (ref "X-SOUTH") (pin "50") (pinfunction "50_50") (pintype "bidirectional"))
    )
    (net (code "171") (name "S13_N") (class "Default")
      (node (ref "SENSOR") (pin "A19") (pinfunction "OUT23_N_A19") (pintype "output"))
      (node (ref "X-SOUTH") (pin "53") (pinfunction "53_53") (pintype "bidirectional"))
    )
    (net (code "172") (name "S13_P") (class "Default")
      (node (ref "SENSOR") (pin "A20") (pinfunction "OUT23_P_A20") (pintype "output"))
      (node (ref "X-SOUTH") (pin "51") (pinfunction "51_51") (pintype "bidirectional"))
    )
    (net (code "173") (name "S14_N") (class "Default")
      (node (ref "SENSOR") (pin "C19") (pinfunction "OUT25_N_C19") (pintype "output"))
      (node (ref "X-SOUTH") (pin "58") (pinfunction "58_58") (pintype "bidirectional"))
    )
    (net (code "174") (name "S14_P") (class "Default")
      (node (ref "SENSOR") (pin "C20") (pinfunction "OUT25_P_C20") (pintype "output"))
      (node (ref "X-SOUTH") (pin "56") (pinfunction "56_56") (pintype "bidirectional"))
    )
    (net (code "175") (name "S15_N") (class "Default")
      (node (ref "SENSOR") (pin "B18") (pinfunction "OUT22_N_B18") (pintype "output"))
      (node (ref "X-SOUTH") (pin "59") (pinfunction "59_59") (pintype "bidirectional"))
    )
    (net (code "176") (name "S15_P") (class "Default")
      (node (ref "SENSOR") (pin "B19") (pinfunction "OUT22_P_B19") (pintype "output"))
      (node (ref "X-SOUTH") (pin "57") (pinfunction "57_57") (pintype "bidirectional"))
    )
    (net (code "177") (name "S16_N") (class "Default")
      (node (ref "SENSOR") (pin "C17") (pinfunction "OUT21_N_C17") (pintype "output"))
      (node (ref "X-SOUTH") (pin "64") (pinfunction "64_64") (pintype "bidirectional"))
    )
    (net (code "178") (name "S16_P") (class "Default")
      (node (ref "SENSOR") (pin "C18") (pinfunction "OUT21_P_C18") (pintype "output"))
      (node (ref "X-SOUTH") (pin "62") (pinfunction "62_62") (pintype "bidirectional"))
    )
    (net (code "179") (name "S17_N") (class "Default")
      (node (ref "SENSOR") (pin "A17") (pinfunction "OUT19_N_A17") (pintype "output"))
      (node (ref "X-SOUTH") (pin "65") (pinfunction "65_65") (pintype "bidirectional"))
    )
    (net (code "180") (name "S17_P") (class "Default")
      (node (ref "SENSOR") (pin "A18") (pinfunction "OUT19_P_A18") (pintype "output"))
      (node (ref "X-SOUTH") (pin "63") (pinfunction "63_63") (pintype "bidirectional"))
    )
    (net (code "181") (name "S18_N") (class "Default")
      (node (ref "SENSOR") (pin "D17") (pinfunction "OUT20_N_D17") (pintype "output"))
      (node (ref "X-SOUTH") (pin "70") (pinfunction "70_70") (pintype "bidirectional"))
    )
    (net (code "182") (name "S18_P") (class "Default")
      (node (ref "SENSOR") (pin "D18") (pinfunction "OUT20_P_D18") (pintype "output"))
      (node (ref "X-SOUTH") (pin "68") (pinfunction "68_68") (pintype "bidirectional"))
    )
    (net (code "183") (name "S19_N") (class "Default")
      (node (ref "SENSOR") (pin "B16") (pinfunction "OUT18_N_B16") (pintype "output"))
      (node (ref "X-SOUTH") (pin "71") (pinfunction "71_71") (pintype "bidirectional"))
    )
    (net (code "184") (name "S19_P") (class "Default")
      (node (ref "SENSOR") (pin "B17") (pinfunction "OUT18_P_B17") (pintype "output"))
      (node (ref "X-SOUTH") (pin "69") (pinfunction "69_69") (pintype "bidirectional"))
    )
    (net (code "185") (name "S20_N") (class "Default")
      (node (ref "SENSOR") (pin "D15") (pinfunction "OUT17_N_D15") (pintype "output"))
      (node (ref "X-SOUTH") (pin "76") (pinfunction "76_76") (pintype "bidirectional"))
    )
    (net (code "186") (name "S20_P") (class "Default")
      (node (ref "SENSOR") (pin "D16") (pinfunction "OUT17_P_D16") (pintype "output"))
      (node (ref "X-SOUTH") (pin "74") (pinfunction "74_74") (pintype "bidirectional"))
    )
    (net (code "187") (name "S21_N") (class "Default")
      (node (ref "SENSOR") (pin "B14") (pinfunction "OUT16_N_B14") (pintype "output"))
      (node (ref "X-SOUTH") (pin "77") (pinfunction "77_77") (pintype "bidirectional"))
    )
    (net (code "188") (name "S21_P") (class "Default")
      (node (ref "SENSOR") (pin "B15") (pinfunction "OUT16_P_B15") (pintype "output"))
      (node (ref "X-SOUTH") (pin "75") (pinfunction "75_75") (pintype "bidirectional"))
    )
    (net (code "189") (name "S22_N") (class "Default")
      (node (ref "SENSOR") (pin "D13") (pinfunction "OUT15_N_D13") (pintype "output"))
      (node (ref "X-SOUTH") (pin "82") (pinfunction "82_82") (pintype "bidirectional"))
    )
    (net (code "190") (name "S22_P") (class "Default")
      (node (ref "SENSOR") (pin "D14") (pinfunction "OUT15_P_D14") (pintype "output"))
      (node (ref "X-SOUTH") (pin "80") (pinfunction "80_80") (pintype "bidirectional"))
    )
    (net (code "191") (name "S23_N") (class "Default")
      (node (ref "SENSOR") (pin "A13") (pinfunction "OUT13_N_A13") (pintype "output"))
      (node (ref "X-SOUTH") (pin "83") (pinfunction "83_83") (pintype "bidirectional"))
    )
    (net (code "192") (name "S23_P") (class "Default")
      (node (ref "SENSOR") (pin "A14") (pinfunction "OUT13_P_A14") (pintype "output"))
      (node (ref "X-SOUTH") (pin "81") (pinfunction "81_81") (pintype "bidirectional"))
    )
    (net (code "193") (name "S24_N") (class "Default")
      (node (ref "SENSOR") (pin "C13") (pinfunction "OUT14_N_C13") (pintype "output"))
      (node (ref "X-SOUTH") (pin "88") (pinfunction "88_88") (pintype "bidirectional"))
    )
    (net (code "194") (name "S24_P") (class "Default")
      (node (ref "SENSOR") (pin "C14") (pinfunction "OUT14_P_C14") (pintype "output"))
      (node (ref "X-SOUTH") (pin "86") (pinfunction "86_86") (pintype "bidirectional"))
    )
    (net (code "195") (name "S25_N") (class "Default")
      (node (ref "SENSOR") (pin "B12") (pinfunction "OUT12_N_B12") (pintype "output"))
      (node (ref "X-SOUTH") (pin "89") (pinfunction "89_89") (pintype "bidirectional"))
    )
    (net (code "196") (name "S25_P") (class "Default")
      (node (ref "SENSOR") (pin "B13") (pinfunction "OUT12_P_B13") (pintype "output"))
      (node (ref "X-SOUTH") (pin "87") (pinfunction "87_87") (pintype "bidirectional"))
    )
    (net (code "197") (name "S26_N") (class "Default")
      (node (ref "SENSOR") (pin "D11") (pinfunction "OUT10_N_D11") (pintype "output"))
      (node (ref "X-SOUTH") (pin "94") (pinfunction "94_94") (pintype "bidirectional"))
    )
    (net (code "198") (name "S26_P") (class "Default")
      (node (ref "SENSOR") (pin "D12") (pinfunction "OUT10_P_D12") (pintype "output"))
      (node (ref "X-SOUTH") (pin "92") (pinfunction "92_92") (pintype "bidirectional"))
    )
    (net (code "199") (name "S27_N") (class "Default")
      (node (ref "SENSOR") (pin "A11") (pinfunction "OUT9_N_A11") (pintype "output"))
      (node (ref "X-SOUTH") (pin "95") (pinfunction "95_95") (pintype "bidirectional"))
    )
    (net (code "200") (name "S27_P") (class "Default")
      (node (ref "SENSOR") (pin "A12") (pinfunction "OUT9_P_A12") (pintype "output"))
      (node (ref "X-SOUTH") (pin "93") (pinfunction "93_93") (pintype "bidirectional"))
    )
    (net (code "201") (name "S28_N") (class "Default")
      (node (ref "SENSOR") (pin "C11") (pinfunction "OUT11_N_C11") (pintype "output"))
      (node (ref "X-SOUTH") (pin "100") (pinfunction "100_100") (pintype "bidirectional"))
    )
    (net (code "202") (name "S28_P") (class "Default")
      (node (ref "SENSOR") (pin "C12") (pinfunction "OUT11_P_C12") (pintype "output"))
      (node (ref "X-SOUTH") (pin "98") (pinfunction "98_98") (pintype "bidirectional"))
    )
    (net (code "203") (name "S29_N") (class "Default")
      (node (ref "SENSOR") (pin "B10") (pinfunction "OUT8_N_B10") (pintype "output"))
      (node (ref "X-SOUTH") (pin "101") (pinfunction "101_101") (pintype "bidirectional"))
    )
    (net (code "204") (name "S29_P") (class "Default")
      (node (ref "SENSOR") (pin "B11") (pinfunction "OUT8_P_B11") (pintype "output"))
      (node (ref "X-SOUTH") (pin "99") (pinfunction "99_99") (pintype "bidirectional"))
    )
    (net (code "205") (name "S30_N") (class "Default")
      (node (ref "SENSOR") (pin "C9") (pinfunction "OUT7_N_C9") (pintype "output"))
      (node (ref "X-SOUTH") (pin "106") (pinfunction "106_106") (pintype "bidirectional"))
    )
    (net (code "206") (name "S30_P") (class "Default")
      (node (ref "SENSOR") (pin "C10") (pinfunction "OUT7_P_C10") (pintype "output"))
      (node (ref "X-SOUTH") (pin "104") (pinfunction "104_104") (pintype "bidirectional"))
    )
    (net (code "207") (name "S31_N") (class "Default")
      (node (ref "SENSOR") (pin "B8") (pinfunction "OUT5_N_B8") (pintype "output"))
      (node (ref "X-SOUTH") (pin "107") (pinfunction "107_107") (pintype "bidirectional"))
    )
    (net (code "208") (name "S31_P") (class "Default")
      (node (ref "SENSOR") (pin "B9") (pinfunction "OUT5_P_B9") (pintype "output"))
      (node (ref "X-SOUTH") (pin "105") (pinfunction "105_105") (pintype "bidirectional"))
    )
    (net (code "209") (name "S32_N") (class "Default")
      (node (ref "SENSOR") (pin "D9") (pinfunction "OUT6_N_D9") (pintype "output"))
      (node (ref "X-SOUTH") (pin "112") (pinfunction "112_112") (pintype "bidirectional"))
    )
    (net (code "210") (name "S32_P") (class "Default")
      (node (ref "SENSOR") (pin "D10") (pinfunction "OUT6_P_D10") (pintype "output"))
      (node (ref "X-SOUTH") (pin "110") (pinfunction "110_110") (pintype "bidirectional"))
    )
    (net (code "211") (name "S33_N") (class "Default")
      (node (ref "SENSOR") (pin "A7") (pinfunction "OUT2_N_A7") (pintype "output"))
      (node (ref "X-SOUTH") (pin "113") (pinfunction "113_113") (pintype "bidirectional"))
    )
    (net (code "212") (name "S33_P") (class "Default")
      (node (ref "SENSOR") (pin "A8") (pinfunction "OUT2_P_A8") (pintype "output"))
      (node (ref "X-SOUTH") (pin "111") (pinfunction "111_111") (pintype "bidirectional"))
    )
    (net (code "213") (name "S34_N") (class "Default")
      (node (ref "SENSOR") (pin "C7") (pinfunction "OUT4_N_C7") (pintype "output"))
      (node (ref "X-SOUTH") (pin "118") (pinfunction "118_118") (pintype "bidirectional"))
    )
    (net (code "214") (name "S34_P") (class "Default")
      (node (ref "SENSOR") (pin "C8") (pinfunction "OUT4_P_C8") (pintype "output"))
      (node (ref "X-SOUTH") (pin "116") (pinfunction "116_116") (pintype "bidirectional"))
    )
    (net (code "215") (name "S35_N") (class "Default")
      (node (ref "SENSOR") (pin "B6") (pinfunction "OUT1_N_B6") (pintype "output"))
      (node (ref "X-SOUTH") (pin "119") (pinfunction "119_119") (pintype "bidirectional"))
    )
    (net (code "216") (name "S35_P") (class "Default")
      (node (ref "SENSOR") (pin "B7") (pinfunction "OUT1_P_B7") (pintype "output"))
      (node (ref "X-SOUTH") (pin "117") (pinfunction "117_117") (pintype "bidirectional"))
    )
    (net (code "217") (name "S36_N") (class "Default")
      (node (ref "SENSOR") (pin "D7") (pinfunction "OUT3_N_D7") (pintype "output"))
      (node (ref "X-SOUTH") (pin "124") (pinfunction "124_124") (pintype "bidirectional"))
    )
    (net (code "218") (name "S36_P") (class "Default")
      (node (ref "SENSOR") (pin "D8") (pinfunction "OUT3_P_D8") (pintype "output"))
      (node (ref "X-SOUTH") (pin "122") (pinfunction "122_122") (pintype "bidirectional"))
    )
    (net (code "219") (name "S37_N") (class "Default")
      (node (ref "SENSOR") (pin "A5") (pinfunction "OUTCTR_N_A5") (pintype "output"))
      (node (ref "X-SOUTH") (pin "125") (pinfunction "125_125") (pintype "bidirectional"))
    )
    (net (code "220") (name "S37_P") (class "Default")
      (node (ref "SENSOR") (pin "A6") (pinfunction "OUTCTR_P_A6") (pintype "output"))
      (node (ref "X-SOUTH") (pin "123") (pinfunction "123_123") (pintype "bidirectional"))
    )
    (net (code "221") (name "S38_N") (class "Default")
      (node (ref "X-SOUTH") (pin "130") (pinfunction "130_130") (pintype "bidirectional"))
    )
    (net (code "222") (name "S38_P") (class "Default")
      (node (ref "X-SOUTH") (pin "128") (pinfunction "128_128") (pintype "bidirectional"))
    )
    (net (code "223") (name "S39_N") (class "Default")
      (node (ref "U3") (pin "6") (pinfunction "EN_6") (pintype "input"))
      (node (ref "X-SOUTH") (pin "131") (pinfunction "131_131") (pintype "bidirectional"))
    )
    (net (code "224") (name "S39_P") (class "Default")
      (node (ref "X-SOUTH") (pin "129") (pinfunction "129_129") (pintype "bidirectional"))
    )
    (net (code "225") (name "SPI_CLK") (class "Default")
      (node (ref "SENSOR") (pin "H29") (pinfunction "SPI_CLK_H29") (pintype "input"))
      (node (ref "U4") (pin "9") (pinfunction "B4_9") (pintype "bidirectional"))
    )
    (net (code "226") (name "SPI_EN") (class "Default")
      (node (ref "SENSOR") (pin "F28") (pinfunction "SPI_EN_F28") (pintype "input"))
      (node (ref "U4") (pin "12") (pinfunction "B1_12") (pintype "bidirectional"))
    )
    (net (code "227") (name "SPI_IN") (class "Default")
      (node (ref "SENSOR") (pin "E28") (pinfunction "SPI_IN_E28") (pintype "input"))
      (node (ref "U4") (pin "10") (pinfunction "B3_10") (pintype "bidirectional"))
    )
    (net (code "228") (name "SPI_OUT") (class "Default")
      (node (ref "SENSOR") (pin "G28") (pinfunction "SPI_OUT_G28") (pintype "output"))
      (node (ref "U4") (pin "11") (pinfunction "B2_11") (pintype "bidirectional"))
    )
    (net (code "229") (name "SYS_RES_N") (class "Default")
      (node (ref "SENSOR") (pin "F30") (pinfunction "SYS_RES_N_F30") (pintype "input"))
      (node (ref "U5") (pin "10") (pinfunction "B3_10") (pintype "bidirectional"))
    )
    (net (code "230") (name "S_CHK_EN") (class "Default")
      (node (ref "X-SOUTH") (pin "8") (pinfunction "8_8") (pintype "bidirectional"))
    )
    (net (code "231") (name "S_CHK_V") (class "Default")
      (node (ref "C5") (pin "1") (pinfunction "1_1") (pintype "passive"))
      (node (ref "C6") (pin "1") (pinfunction "1_1") (pintype "passive"))
      (node (ref "C7") (pin "1") (pinfunction "1_1") (pintype "passive"))
      (node (ref "R20") (pin "1") (pinfunction "1_1") (pintype "passive"))
      (node (ref "TP3") (pin "TP") (pinfunction "TP_TP") (pintype "input"))
      (node (ref "USE") (pin "8") (pinfunction "VDD_8") (pintype "power_in"))
      (node (ref "USS") (pin "8") (pinfunction "VDD_8") (pintype "power_in"))
      (node (ref "USW") (pin "8") (pinfunction "VDD_8") (pintype "power_in"))
      (node (ref "X-SOUTH") (pin "10") (pinfunction "10_10") (pintype "bidirectional"))
    )
    (net (code "232") (name "S_I2C_EN") (class "Default")
      (node (ref "X-SOUTH") (pin "137") (pinfunction "137_137") (pintype "bidirectional"))
    )
    (net (code "233") (name "S_I2C_V") (class "Default")
      (node (ref "U7") (pin "8") (pinfunction "VCC_8") (pintype "power_in"))
      (node (ref "X-SOUTH") (pin "135") (pinfunction "135_135") (pintype "bidirectional"))
    )
    (net (code "234") (name "S_REF") (class "Default")
      (node (ref "R20") (pin "2") (pinfunction "2_2") (pintype "passive"))
      (node (ref "TP4") (pin "TP") (pinfunction "TP_TP") (pintype "input"))
      (node (ref "U2") (pin "1") (pinfunction "CATHODE_1") (pintype "output"))
      (node (ref "U2") (pin "3") (pinfunction "REF_3") (pintype "input"))
      (node (ref "USE") (pin "2") (pinfunction "VINA-_2") (pintype "input"))
      (node (ref "USE") (pin "5") (pinfunction "VINB+_5") (pintype "input"))
      (node (ref "USS") (pin "2") (pinfunction "VINA-_2") (pintype "input"))
      (node (ref "USS") (pin "5") (pinfunction "VINB+_5") (pintype "input"))
      (node (ref "USW") (pin "2") (pinfunction "VINA-_2") (pintype "input"))
      (node (ref "USW") (pin "5") (pinfunction "VINB+_5") (pintype "input"))
    )
    (net (code "235") (name "S_SCK") (class "Default")
      (node (ref "X-SOUTH") (pin "144") (pinfunction "144_144") (pintype "bidirectional"))
    )
    (net (code "236") (name "S_SCL") (class "Default")
      (node (ref "U7") (pin "2") (pinfunction "SCL_2") (pintype "input"))
      (node (ref "X-SOUTH") (pin "143") (pinfunction "143_143") (pintype "bidirectional"))
    )
    (net (code "237") (name "S_SDA") (class "Default")
      (node (ref "U7") (pin "1") (pinfunction "SDA_1") (pintype "bidirectional"))
      (node (ref "X-SOUTH") (pin "141") (pinfunction "141_141") (pintype "bidirectional"))
    )
    (net (code "238") (name "S_SDI") (class "Default")
      (node (ref "X-SOUTH") (pin "140") (pinfunction "140_140") (pintype "bidirectional"))
    )
    (net (code "239") (name "S_SDO") (class "Default")
      (node (ref "X-SOUTH") (pin "142") (pinfunction "142_142") (pintype "bidirectional"))
    )
    (net (code "240") (name "S_SPI_EN") (class "Default")
      (node (ref "X-SOUTH") (pin "136") (pinfunction "136_136") (pintype "bidirectional"))
    )
    (net (code "241") (name "S_SPI_V") (class "Default")
      (node (ref "X-SOUTH") (pin "134") (pinfunction "134_134") (pintype "bidirectional"))
    )
    (net (code "242") (name "S_VE") (class "Default")
      (node (ref "X-SOUTH") (pin "13") (pinfunction "13_13") (pintype "bidirectional"))
      (node (ref "X-SOUTH") (pin "19") (pinfunction "19_19") (pintype "bidirectional"))
      (node (ref "X-SOUTH") (pin "25") (pinfunction "25_25") (pintype "bidirectional"))
      (node (ref "X-SOUTH") (pin "31") (pinfunction "31_31") (pintype "bidirectional"))
      (node (ref "X-SOUTH") (pin "37") (pinfunction "37_37") (pintype "bidirectional"))
    )
    (net (code "243") (name "S_VE_CV") (class "Default")
      (node (ref "C11") (pin "1") (pinfunction "1_1") (pintype "passive"))
      (node (ref "R10") (pin "1") (pinfunction "1_1") (pintype "passive"))
      (node (ref "X-SOUTH") (pin "2") (pinfunction "2_2") (pintype "bidirectional"))
    )
    (net (code "244") (name "S_VE_OV") (class "Default")
      (node (ref "USE") (pin "7") (pinfunction "OUTB_7") (pintype "output"))
      (node (ref "X-SOUTH") (pin "1") (pinfunction "1_1") (pintype "bidirectional"))
    )
    (net (code "245") (name "S_VE_UV") (class "Default")
      (node (ref "USE") (pin "1") (pinfunction "OUTA_1") (pintype "output"))
      (node (ref "X-SOUTH") (pin "7") (pinfunction "7_7") (pintype "bidirectional"))
    )
    (net (code "246") (name "S_VS") (class "Default")
      (node (ref "C45") (pin "1") (pinfunction "1_1") (pintype "passive"))
      (node (ref "C46") (pin "1") (pinfunction "1_1") (pintype "passive"))
      (node (ref "C47") (pin "1") (pinfunction "1_1") (pintype "passive"))
      (node (ref "C48") (pin "1") (pinfunction "1_1") (pintype "passive"))
      (node (ref "C49") (pin "1") (pinfunction "1_1") (pintype "passive"))
      (node (ref "C72") (pin "1") (pinfunction "1_1") (pintype "passive"))
      (node (ref "C73") (pin "1") (pinfunction "1_1") (pintype "passive"))
      (node (ref "C74") (pin "1") (pinfunction "1_1") (pintype "passive"))
      (node (ref "C81") (pin "1") (pinfunction "1_1") (pintype "passive"))
      (node (ref "C82") (pin "1") (pinfunction "1_1") (pintype "passive"))
      (node (ref "C83") (pin "1") (pinfunction "1_1") (pintype "passive"))
      (node (ref "SENSOR") (pin "A30") (pinfunction "VDD_PIX_A30") (pintype "power_in"))
      (node (ref "SENSOR") (pin "D28") (pinfunction "VDD_PIX_D28") (pintype "power_in"))
      (node (ref "SENSOR") (pin "D30") (pinfunction "VDD_PIX_D30") (pintype "power_in"))
      (node (ref "SENSOR") (pin "G1") (pinfunction "VDD_PIX_G1") (pintype "power_in"))
      (node (ref "SENSOR") (pin "H28") (pinfunction "VDD_PIX_H28") (pintype "power_in"))
      (node (ref "TP6") (pin "TP") (pinfunction "TP_TP") (pintype "input"))
      (node (ref "X-SOUTH") (pin "49") (pinfunction "49_49") (pintype "bidirectional"))
      (node (ref "X-SOUTH") (pin "55") (pinfunction "55_55") (pintype "bidirectional"))
      (node (ref "X-SOUTH") (pin "61") (pinfunction "61_61") (pintype "bidirectional"))
      (node (ref "X-SOUTH") (pin "67") (pinfunction "67_67") (pintype "bidirectional"))
      (node (ref "X-SOUTH") (pin "73") (pinfunction "73_73") (pintype "bidirectional"))
      (node (ref "X-SOUTH") (pin "79") (pinfunction "79_79") (pintype "bidirectional"))
      (node (ref "X-SOUTH") (pin "85") (pinfunction "85_85") (pintype "bidirectional"))
      (node (ref "X-SOUTH") (pin "91") (pinfunction "91_91") (pintype "bidirectional"))
      (node (ref "X-SOUTH") (pin "97") (pinfunction "97_97") (pintype "bidirectional"))
    )
    (net (code "247") (name "S_VS_CV") (class "Default")
      (node (ref "C12") (pin "1") (pinfunction "1_1") (pintype "passive"))
      (node (ref "R13") (pin "1") (pinfunction "1_1") (pintype "passive"))
      (node (ref "X-SOUTH") (pin "4") (pinfunction "4_4") (pintype "bidirectional"))
    )
    (net (code "248") (name "S_VS_OV") (class "Default")
      (node (ref "USS") (pin "7") (pinfunction "OUTB_7") (pintype "output"))
      (node (ref "X-SOUTH") (pin "3") (pinfunction "3_3") (pintype "bidirectional"))
    )
    (net (code "249") (name "S_VS_UV") (class "Default")
      (node (ref "USS") (pin "1") (pinfunction "OUTA_1") (pintype "output"))
      (node (ref "X-SOUTH") (pin "9") (pinfunction "9_9") (pintype "bidirectional"))
    )
    (net (code "250") (name "S_VW") (class "Default")
      (node (ref "C90") (pin "1") (pinfunction "1_1") (pintype "passive"))
      (node (ref "U3") (pin "1") (pinfunction "BIAS_1") (pintype "power_in"))
      (node (ref "U3") (pin "3") (pinfunction "IN_3") (pintype "power_in"))
      (node (ref "X-SOUTH") (pin "109") (pinfunction "109_109") (pintype "bidirectional"))
      (node (ref "X-SOUTH") (pin "115") (pinfunction "115_115") (pintype "bidirectional"))
      (node (ref "X-SOUTH") (pin "121") (pinfunction "121_121") (pintype "bidirectional"))
      (node (ref "X-SOUTH") (pin "127") (pinfunction "127_127") (pintype "bidirectional"))
      (node (ref "X-SOUTH") (pin "133") (pinfunction "133_133") (pintype "bidirectional"))
    )
    (net (code "251") (name "S_VW_CV") (class "Default")
      (node (ref "C13") (pin "1") (pinfunction "1_1") (pintype "passive"))
      (node (ref "R16") (pin "1") (pinfunction "1_1") (pintype "passive"))
      (node (ref "X-SOUTH") (pin "6") (pinfunction "6_6") (pintype "bidirectional"))
    )
    (net (code "252") (name "S_VW_OV") (class "Default")
      (node (ref "USW") (pin "7") (pinfunction "OUTB_7") (pintype "output"))
      (node (ref "X-SOUTH") (pin "5") (pinfunction "5_5") (pintype "bidirectional"))
    )
    (net (code "253") (name "S_VW_UV") (class "Default")
      (node (ref "USW") (pin "1") (pinfunction "OUTA_1") (pintype "output"))
      (node (ref "X-SOUTH") (pin "11") (pinfunction "11_11") (pintype "bidirectional"))
    )
    (net (code "254") (name "TDIG1") (class "Default")
      (node (ref "SENSOR") (pin "G27") (pinfunction "TDIG1_G27") (pintype "output"))
      (node (ref "U5") (pin "9") (pinfunction "B4_9") (pintype "bidirectional"))
    )
    (net (code "255") (name "TDIG2") (class "Default")
      (node (ref "SENSOR") (pin "G26") (pinfunction "TDIG2_G26") (pintype "output"))
      (node (ref "U6") (pin "11") (pinfunction "B2_11") (pintype "bidirectional"))
    )
    (net (code "256") (name "T_EXP1") (class "Default")
      (node (ref "SENSOR") (pin "H30") (pinfunction "T_EXP1_H30") (pintype "input"))
      (node (ref "U5") (pin "12") (pinfunction "B1_12") (pintype "bidirectional"))
    )
    (net (code "257") (name "T_EXP2") (class "Default")
      (node (ref "SENSOR") (pin "E29") (pinfunction "T_EXP2_E29") (pintype "input"))
      (node (ref "U6") (pin "10") (pinfunction "B3_10") (pintype "bidirectional"))
    )
    (net (code "258") (name "VRAMP1") (class "Default")
      (node (ref "C16") (pin "1") (pinfunction "1_1") (pintype "passive"))
      (node (ref "R23") (pin "1") (pinfunction "1_1") (pintype "passive"))
      (node (ref "SENSOR") (pin "G29") (pinfunction "VRAMP1_G29") (pintype "bidirectional"))
    )
    (net (code "259") (name "VRAMP2") (class "Default")
      (node (ref "C17") (pin "1") (pinfunction "1_1") (pintype "passive"))
      (node (ref "R23") (pin "2") (pinfunction "2_2") (pintype "passive"))
      (node (ref "SENSOR") (pin "F29") (pinfunction "VRAMP2_F29") (pintype "bidirectional"))
    )
    (net (code "260") (name "VTREF") (class "Default")
      (node (ref "C65") (pin "1") (pinfunction "1_1") (pintype "passive"))
      (node (ref "C91") (pin "2") (pinfunction "2_2") (pintype "passive"))
      (node (ref "R21") (pin "2") (pinfunction "2_2") (pintype "passive"))
      (node (ref "R24") (pin "1") (pinfunction "1_1") (pintype "passive"))
      (node (ref "SENSOR") (pin "B2") (pinfunction "VTREF_B2") (pintype "bidirectional"))
      (node (ref "U3") (pin "4") (pinfunction "OUT_4") (pintype "power_in"))
    )
    (net (code "261") (name "VTSIG") (class "Default")
      (node (ref "C66") (pin "1") (pinfunction "1_1") (pintype "passive"))
      (node (ref "R24") (pin "2") (pinfunction "2_2") (pintype "passive"))
      (node (ref "SENSOR") (pin "C2") (pinfunction "VTSIG_C2") (pintype "bidirectional"))
    )
    (net (code "262") (name "unconnected-(U1-NC-Pad2)") (class "Default")
      (node (ref "U1") (pin "2") (pinfunction "NC_2") (pintype "no_connect"))
    )
    (net (code "263") (name "unconnected-(U1-NC-Pad4)") (class "Default")
      (node (ref "U1") (pin "4") (pinfunction "NC_4") (pintype "no_connect"))
    )
    (net (code "264") (name "unconnected-(U1-NC-Pad5)") (class "Default")
      (node (ref "U1") (pin "5") (pinfunction "NC_5") (pintype "no_connect"))
    )
    (net (code "265") (name "unconnected-(U2-NC-Pad2)") (class "Default")
      (node (ref "U2") (pin "2") (pinfunction "NC_2") (pintype "no_connect"))
    )
    (net (code "266") (name "unconnected-(U2-NC-Pad4)") (class "Default")
      (node (ref "U2") (pin "4") (pinfunction "NC_4") (pintype "no_connect"))
    )
    (net (code "267") (name "unconnected-(U2-NC-Pad5)") (class "Default")
      (node (ref "U2") (pin "5") (pinfunction "NC_5") (pintype "no_connect"))
    )
    (net (code "268") (name "unconnected-(U7-OS-Pad3)") (class "Default")
      (node (ref "U7") (pin "3") (pinfunction "OS_3") (pintype "output"))
    )
    (net (code "269") (name "unconnected-(X-NORTH-PadM1)") (class "Default")
      (node (ref "X-NORTH") (pin "M1") (pinfunction "M1_M1") (pintype "bidirectional"))
    )
    (net (code "270") (name "unconnected-(X-NORTH-PadM2)") (class "Default")
      (node (ref "X-NORTH") (pin "M2") (pinfunction "M2_M2") (pintype "bidirectional"))
    )
    (net (code "271") (name "unconnected-(X-SOUTH-PadM1)") (class "Default")
      (node (ref "X-SOUTH") (pin "M1") (pinfunction "M1_M1") (pintype "bidirectional"))
    )
    (net (code "272") (name "unconnected-(X-SOUTH-PadM2)") (class "Default")
      (node (ref "X-SOUTH") (pin "M2") (pinfunction "M2_M2") (pintype "bidirectional"))
    )
  )
)
